# moire_v2_4.net
KiCad netlist of a schematic drawn in EAGLE
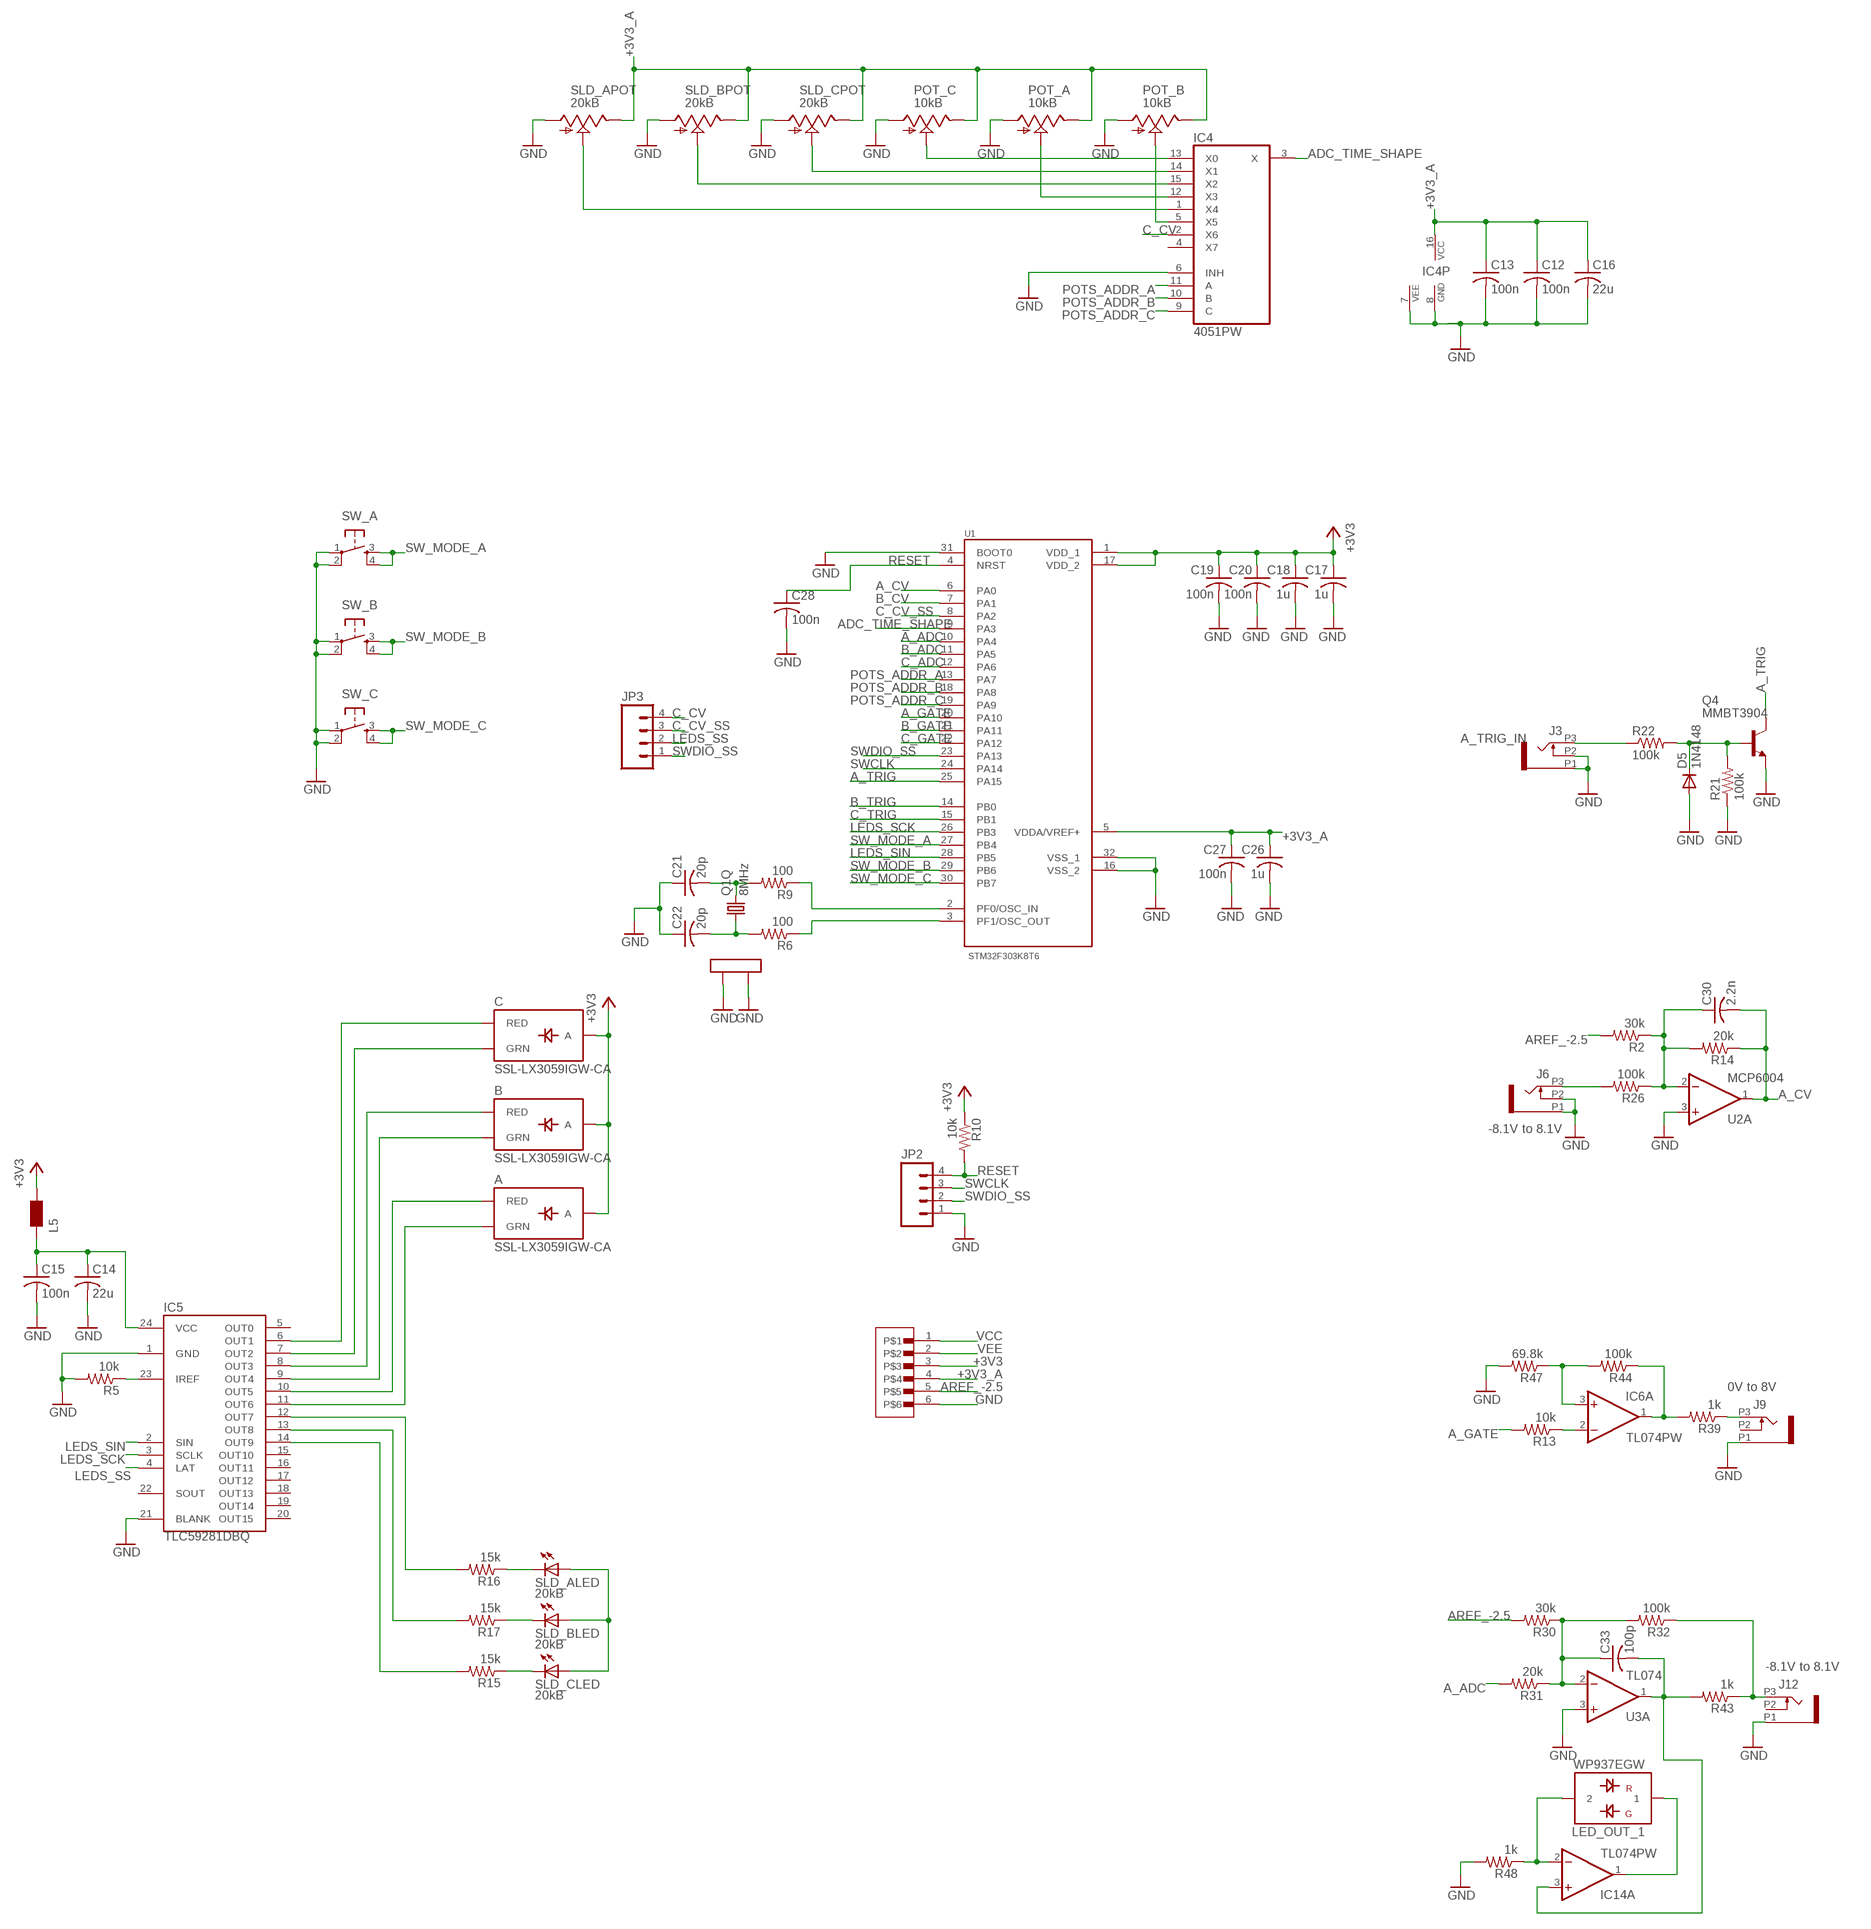
[diagram p0: schematic, sheet 1, part 1 of 2]
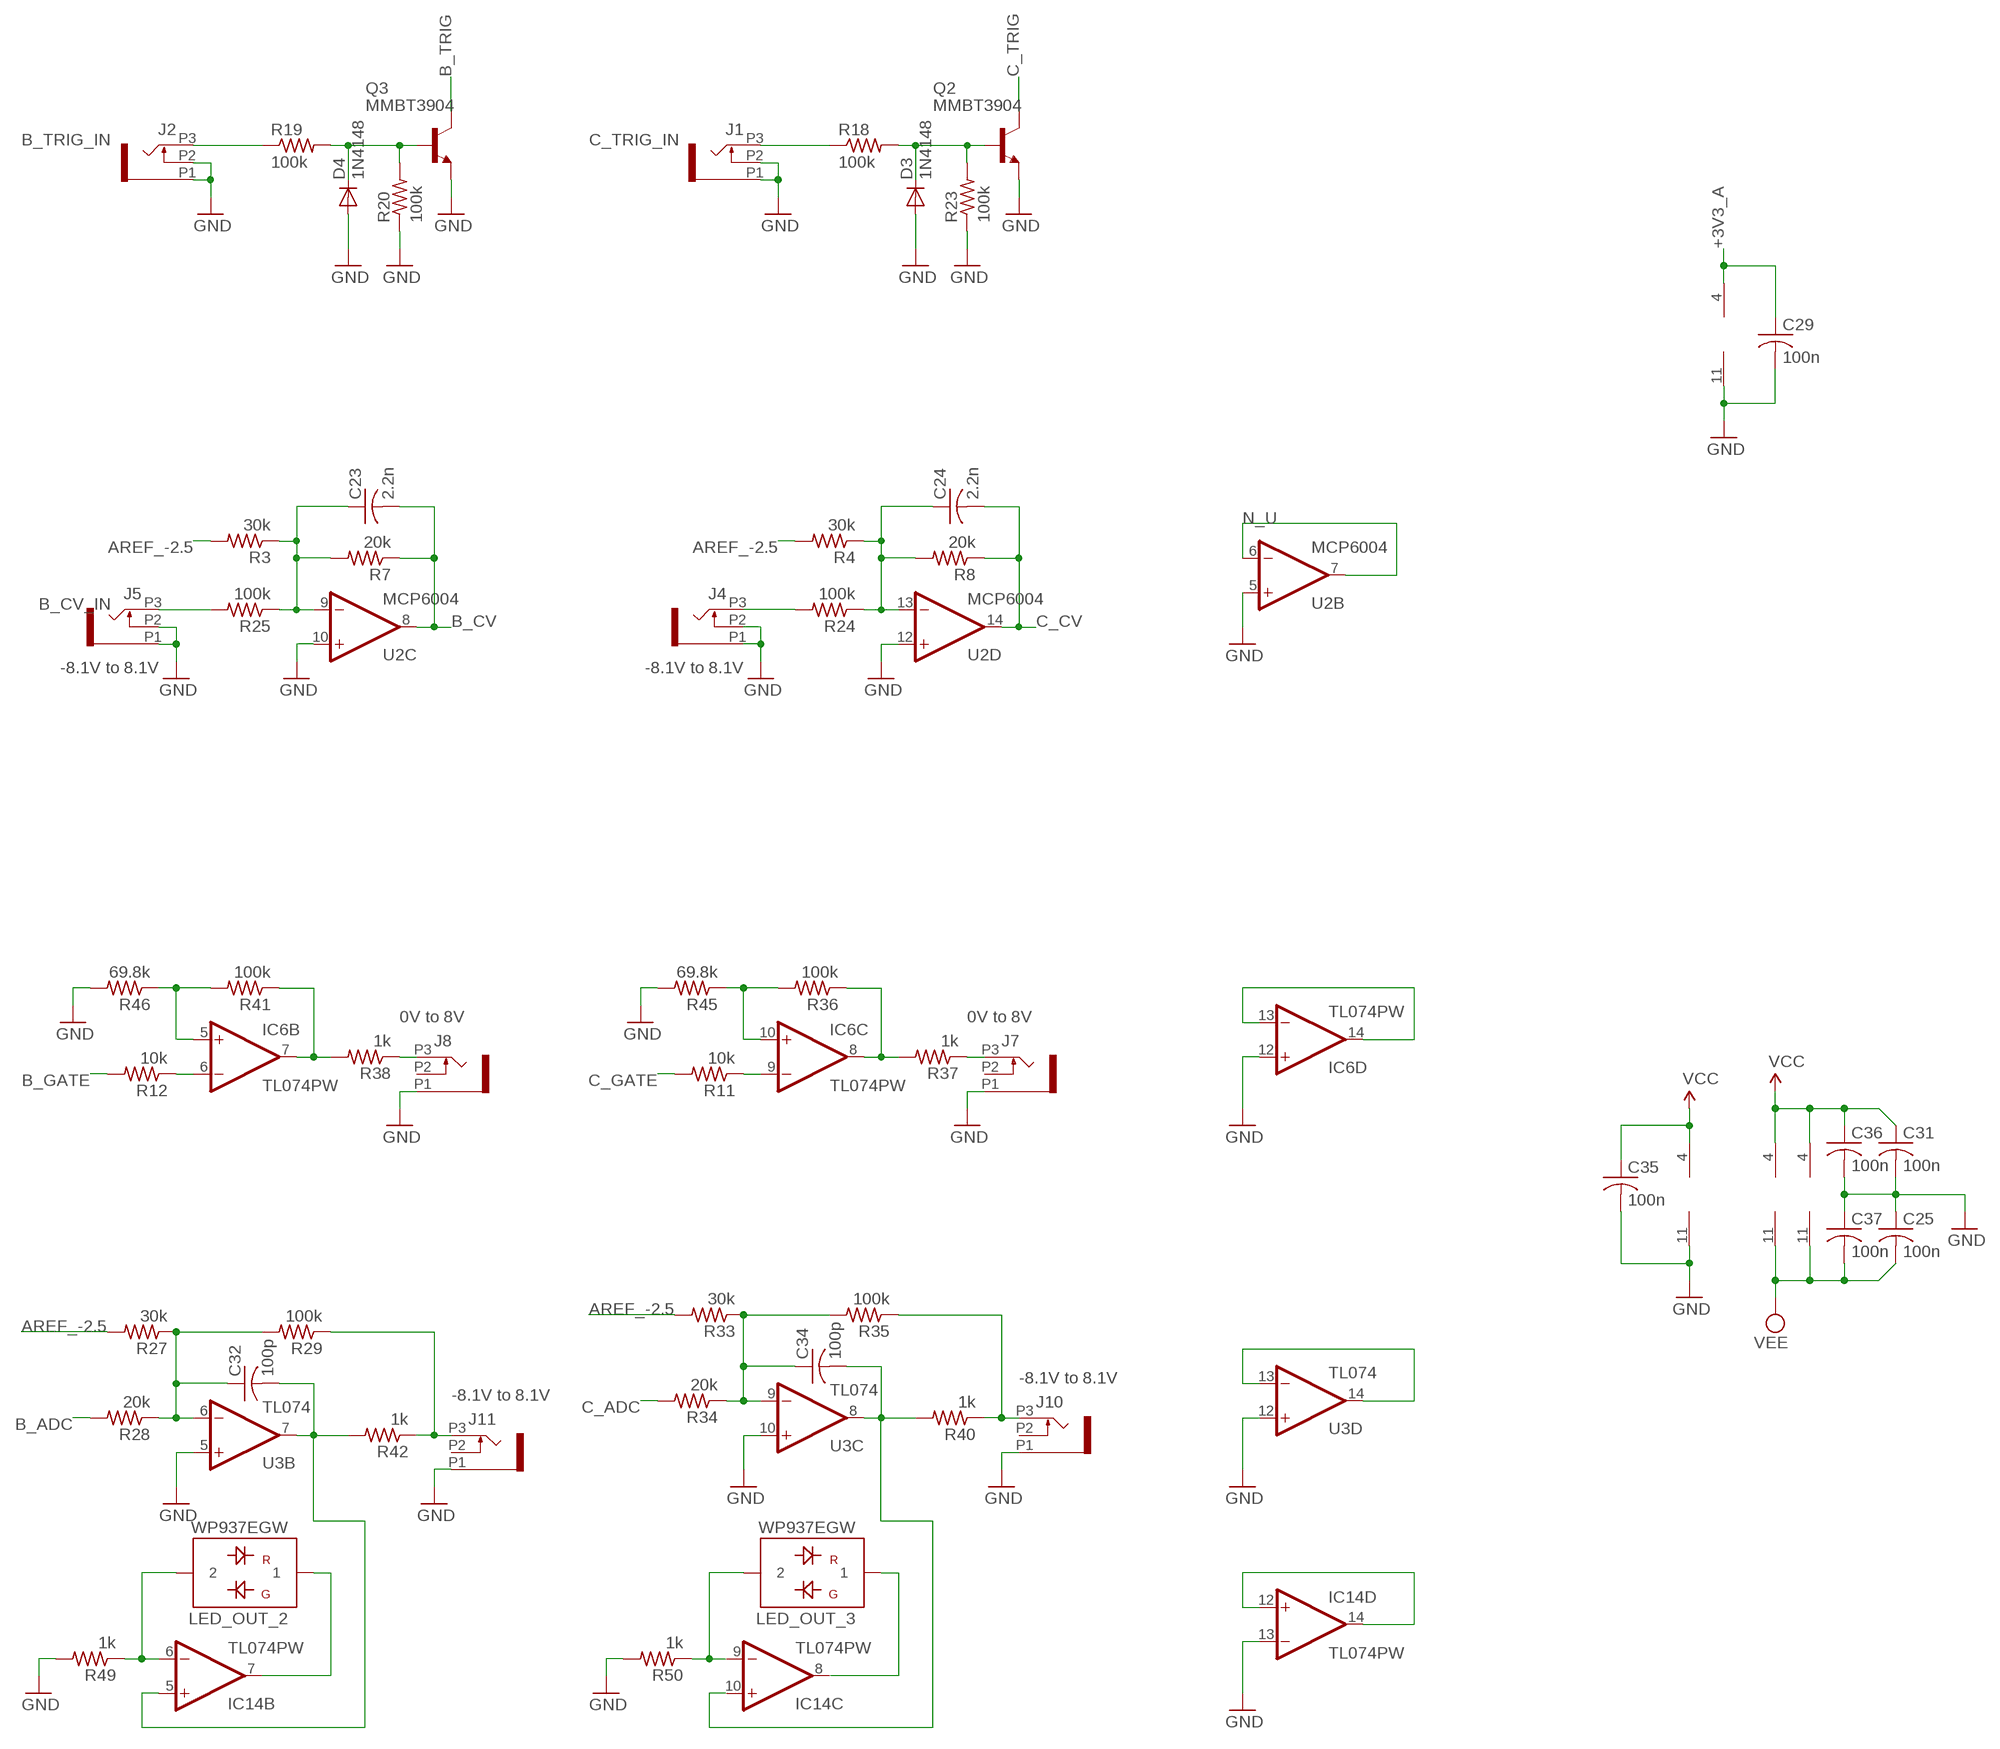
[diagram p1: schematic, sheet 1, part 2 of 2]
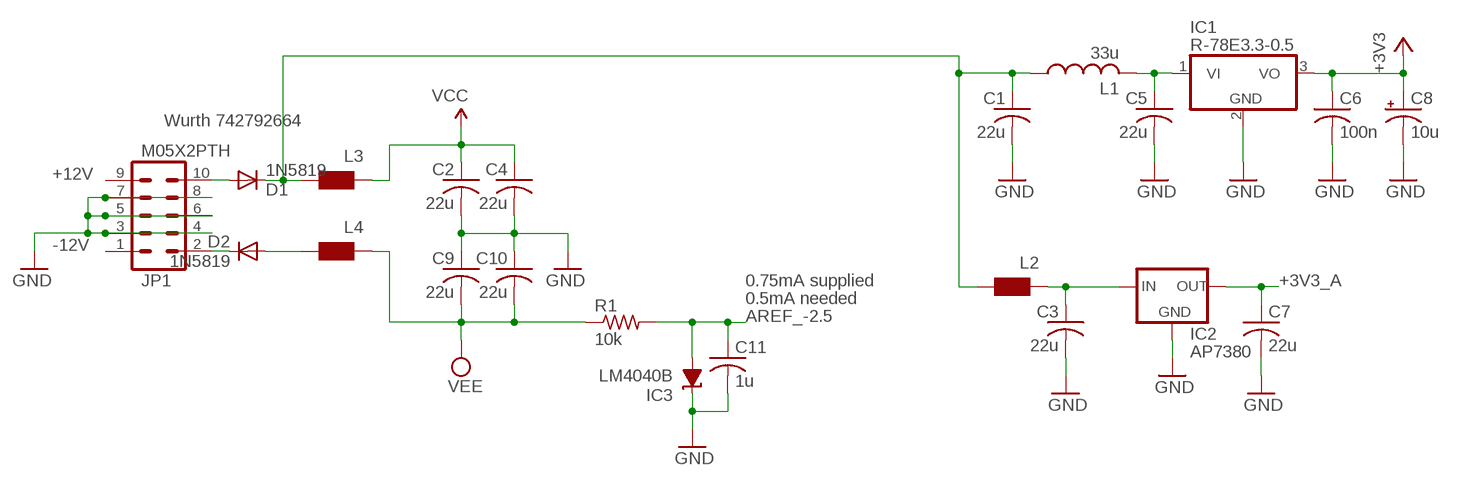
[diagram p2: schematic, sheet 2]

(export (version "E")
  (design (tool "Eeschema 10.0.6"))
  (components
    (comp (ref "C1")
      (value "22u")
      (footprint "eagle-import:RCL_C1206")
      (libsource (lib "eagle-import") (part "RCL_C-USC1206"))
    )
    (comp (ref "C2")
      (value "22u")
      (footprint "eagle-import:RCL_C1206")
      (libsource (lib "eagle-import") (part "RCL_C-USC1206"))
    )
    (comp (ref "C3")
      (value "22u")
      (footprint "eagle-import:RCL_C1206")
      (libsource (lib "eagle-import") (part "RCL_C-USC1206"))
    )
    (comp (ref "C4")
      (value "22u")
      (footprint "eagle-import:RCL_C1206")
      (libsource (lib "eagle-import") (part "RCL_C-USC1206"))
    )
    (comp (ref "C5")
      (value "22u")
      (footprint "eagle-import:RCL_C1206")
      (libsource (lib "eagle-import") (part "RCL_C-USC1206"))
    )
    (comp (ref "C6")
      (value "100n")
      (footprint "eagle-import:RCL_C0603")
      (libsource (lib "eagle-import") (part "RCL_C-USC0603"))
    )
    (comp (ref "C7")
      (value "22u")
      (footprint "eagle-import:RCL_C1206")
      (libsource (lib "eagle-import") (part "RCL_C-USC1206"))
    )
    (comp (ref "C8")
      (value "10u")
      (footprint "eagle-import:RCL_PANASONIC_A")
      (libsource (lib "eagle-import") (part "RCL_CPOL-USA"))
    )
    (comp (ref "C9")
      (value "22u")
      (footprint "eagle-import:RCL_C1206")
      (libsource (lib "eagle-import") (part "RCL_C-USC1206"))
    )
    (comp (ref "C10")
      (value "22u")
      (footprint "eagle-import:RCL_C1206")
      (libsource (lib "eagle-import") (part "RCL_C-USC1206"))
    )
    (comp (ref "C11")
      (value "1u")
      (footprint "eagle-import:RCL_C0603")
      (libsource (lib "eagle-import") (part "RCL_C-USC0603"))
    )
    (comp (ref "D1")
      (value "1N5819")
      (footprint "eagle-import:DIODE_SOD123")
      (libsource (lib "eagle-import") (part "DIODE_DIODE-SOD123"))
    )
    (comp (ref "D2")
      (value "1N5819")
      (footprint "eagle-import:DIODE_SOD123")
      (libsource (lib "eagle-import") (part "DIODE_DIODE-SOD123"))
    )
    (comp (ref "IC1")
      (value "R-78E3.3-0.5")
      (footprint "eagle-import:WE78")
      (libsource (lib "eagle-import") (part "WE173950378"))
    )
    (comp (ref "IC2")
      (value "AP7380")
      (footprint "eagle-import:SOT89")
      (libsource (lib "eagle-import") (part "AP7380"))
    )
    (comp (ref "IC3")
      (value "LM4040B")
      (footprint "eagle-import:DBZ_R-PDSO-G3")
      (libsource (lib "eagle-import") (part "LM4041DBZB12"))
    )
    (comp (ref "JP1")
      (value "M05X2PTH")
      (footprint "eagle-import:2X5-PTH")
      (libsource (lib "eagle-import") (part "M05X2PTH"))
    )
    (comp (ref "L1")
      (value "33u")
      (footprint "eagle-import:L2012C")
      (libsource (lib "eagle-import") (part "L-USL2012C"))
    )
    (comp (ref "L2")
      (value "WE-CBF_0603")
      (footprint "eagle-import:0603")
      (libsource (lib "eagle-import") (part "WE-CBF_0603"))
    )
    (comp (ref "L3")
      (value "WE-CBF_0603")
      (footprint "eagle-import:0603")
      (libsource (lib "eagle-import") (part "WE-CBF_0603"))
    )
    (comp (ref "L4")
      (value "WE-CBF_0603")
      (footprint "eagle-import:0603")
      (libsource (lib "eagle-import") (part "WE-CBF_0603"))
    )
    (comp (ref "R1")
      (value "10k")
      (footprint "eagle-import:RCL_R0603")
      (libsource (lib "eagle-import") (part "RCL_R-US_R0603"))
    )
    (comp (ref "A")
      (value "SSL-LX3059IGW-CA")
      (footprint "eagle-import:LED-BICOLOR-THROUGHHOLE-LUMEX")
      (libsource (lib "eagle-import") (part "LED-BICOLOR-THROUGHHOLE-CA"))
    )
    (comp (ref "B")
      (value "SSL-LX3059IGW-CA")
      (footprint "eagle-import:LED-BICOLOR-THROUGHHOLE-LUMEX")
      (libsource (lib "eagle-import") (part "LED-BICOLOR-THROUGHHOLE-CA"))
    )
    (comp (ref "C")
      (value "SSL-LX3059IGW-CA")
      (footprint "eagle-import:LED-BICOLOR-THROUGHHOLE-LUMEX")
      (libsource (lib "eagle-import") (part "LED-BICOLOR-THROUGHHOLE-CA"))
    )
    (comp (ref "C12")
      (value "100n")
      (footprint "eagle-import:RCL_C0603")
      (libsource (lib "eagle-import") (part "RCL_C-USC0603"))
    )
    (comp (ref "C13")
      (value "100n")
      (footprint "eagle-import:RCL_C0603")
      (libsource (lib "eagle-import") (part "RCL_C-USC0603"))
    )
    (comp (ref "C14")
      (value "22u")
      (footprint "eagle-import:RCL_C1206")
      (libsource (lib "eagle-import") (part "RCL_C-USC1206"))
    )
    (comp (ref "C15")
      (value "100n")
      (footprint "eagle-import:RCL_C0603")
      (libsource (lib "eagle-import") (part "RCL_C-USC0603"))
    )
    (comp (ref "C16")
      (value "22u")
      (footprint "eagle-import:RCL_C1206")
      (libsource (lib "eagle-import") (part "RCL_C-USC1206"))
    )
    (comp (ref "C17")
      (value "1u")
      (footprint "eagle-import:RCL_C0603")
      (libsource (lib "eagle-import") (part "RCL_C-USC0603"))
    )
    (comp (ref "C18")
      (value "1u")
      (footprint "eagle-import:RCL_C0603")
      (libsource (lib "eagle-import") (part "RCL_C-USC0603"))
    )
    (comp (ref "C19")
      (value "100n")
      (footprint "eagle-import:RCL_C0603")
      (libsource (lib "eagle-import") (part "RCL_C-USC0603"))
    )
    (comp (ref "C20")
      (value "100n")
      (footprint "eagle-import:RCL_C0603")
      (libsource (lib "eagle-import") (part "RCL_C-USC0603"))
    )
    (comp (ref "C21")
      (value "20p")
      (footprint "eagle-import:RCL_C0603")
      (libsource (lib "eagle-import") (part "RCL_C-USC0603"))
    )
    (comp (ref "C22")
      (value "20p")
      (footprint "eagle-import:RCL_C0603")
      (libsource (lib "eagle-import") (part "RCL_C-USC0603"))
    )
    (comp (ref "C23")
      (value "2.2n")
      (footprint "eagle-import:RCL_C0603")
      (libsource (lib "eagle-import") (part "RCL_C-USC0603"))
    )
    (comp (ref "C24")
      (value "2.2n")
      (footprint "eagle-import:RCL_C0603")
      (libsource (lib "eagle-import") (part "RCL_C-USC0603"))
    )
    (comp (ref "C25")
      (value "100n")
      (footprint "eagle-import:RCL_C0603")
      (libsource (lib "eagle-import") (part "RCL_C-USC0603"))
    )
    (comp (ref "C26")
      (value "1u")
      (footprint "eagle-import:RCL_C0603")
      (libsource (lib "eagle-import") (part "RCL_C-USC0603"))
    )
    (comp (ref "C27")
      (value "100n")
      (footprint "eagle-import:RCL_C0603")
      (libsource (lib "eagle-import") (part "RCL_C-USC0603"))
    )
    (comp (ref "C28")
      (value "100n")
      (footprint "eagle-import:RCL_C0603")
      (libsource (lib "eagle-import") (part "RCL_C-USC0603"))
    )
    (comp (ref "C29")
      (value "100n")
      (footprint "eagle-import:RCL_C0603")
      (libsource (lib "eagle-import") (part "RCL_C-USC0603"))
    )
    (comp (ref "C30")
      (value "2.2n")
      (footprint "eagle-import:RCL_C0603")
      (libsource (lib "eagle-import") (part "RCL_C-USC0603"))
    )
    (comp (ref "C31")
      (value "100n")
      (footprint "eagle-import:RCL_C0603")
      (libsource (lib "eagle-import") (part "RCL_C-USC0603"))
    )
    (comp (ref "C32")
      (value "100p")
      (footprint "eagle-import:RCL_C0603")
      (libsource (lib "eagle-import") (part "RCL_C-USC0603"))
    )
    (comp (ref "C33")
      (value "100p")
      (footprint "eagle-import:RCL_C0603")
      (libsource (lib "eagle-import") (part "RCL_C-USC0603"))
    )
    (comp (ref "C34")
      (value "100p")
      (footprint "eagle-import:RCL_C0603")
      (libsource (lib "eagle-import") (part "RCL_C-USC0603"))
    )
    (comp (ref "C35")
      (value "100n")
      (footprint "eagle-import:RCL_C0603")
      (libsource (lib "eagle-import") (part "RCL_C-USC0603"))
    )
    (comp (ref "C36")
      (value "100n")
      (footprint "eagle-import:RCL_C0603")
      (libsource (lib "eagle-import") (part "RCL_C-USC0603"))
    )
    (comp (ref "C37")
      (value "100n")
      (footprint "eagle-import:RCL_C0603")
      (libsource (lib "eagle-import") (part "RCL_C-USC0603"))
    )
    (comp (ref "D3")
      (value "1N4148")
      (footprint "eagle-import:DIODE_SOD523")
      (libsource (lib "eagle-import") (part "DIODE_DIODE-SOD523"))
    )
    (comp (ref "D4")
      (value "1N4148")
      (footprint "eagle-import:DIODE_SOD523")
      (libsource (lib "eagle-import") (part "DIODE_DIODE-SOD523"))
    )
    (comp (ref "D5")
      (value "1N4148")
      (footprint "eagle-import:DIODE_SOD523")
      (libsource (lib "eagle-import") (part "DIODE_DIODE-SOD523"))
    )
    (comp (ref "IC4")
      (value "4051PW")
      (footprint "eagle-import:TSSOP16_065")
      (libsource (lib "eagle-import") (part "4051PW"))
    )
    (comp (ref "IC5")
      (value "TLC59281DBQ")
      (footprint "eagle-import:TSSOP24_0635")
      (libsource (lib "eagle-import") (part "TLC59281DBQ"))
    )
    (comp (ref "IC6")
      (value "TL074PW")
      (footprint "eagle-import:TSSOP14_065")
      (libsource (lib "eagle-import") (part "og-linear_TL074PW"))
    )
    (comp (ref "IC14")
      (value "TL074PW")
      (footprint "eagle-import:TSSOP14_065")
      (libsource (lib "eagle-import") (part "TL074PW"))
    )
    (comp (ref "J1")
      (value "PJ301_THONKICONN6")
      (footprint "eagle-import:WQP_PJ_301M6")
      (libsource (lib "eagle-import") (part "PJ301_THONKICONN6"))
    )
    (comp (ref "J2")
      (value "PJ301_THONKICONN6")
      (footprint "eagle-import:WQP_PJ_301M6")
      (libsource (lib "eagle-import") (part "PJ301_THONKICONN6"))
    )
    (comp (ref "J3")
      (value "PJ301_THONKICONN6")
      (footprint "eagle-import:WQP_PJ_301M6")
      (libsource (lib "eagle-import") (part "PJ301_THONKICONN6"))
    )
    (comp (ref "J4")
      (value "PJ301_THONKICONN6")
      (footprint "eagle-import:WQP_PJ_301M6")
      (libsource (lib "eagle-import") (part "PJ301_THONKICONN6"))
    )
    (comp (ref "J5")
      (value "PJ301_THONKICONN6")
      (footprint "eagle-import:WQP_PJ_301M6")
      (libsource (lib "eagle-import") (part "PJ301_THONKICONN6"))
    )
    (comp (ref "J6")
      (value "PJ301_THONKICONN6")
      (footprint "eagle-import:WQP_PJ_301M6")
      (libsource (lib "eagle-import") (part "PJ301_THONKICONN6"))
    )
    (comp (ref "J7")
      (value "PJ301_THONKICONN6")
      (footprint "eagle-import:WQP_PJ_301M6")
      (libsource (lib "eagle-import") (part "PJ301_THONKICONN6"))
    )
    (comp (ref "J8")
      (value "PJ301_THONKICONN6")
      (footprint "eagle-import:WQP_PJ_301M6")
      (libsource (lib "eagle-import") (part "PJ301_THONKICONN6"))
    )
    (comp (ref "J9")
      (value "PJ301_THONKICONN6")
      (footprint "eagle-import:WQP_PJ_301M6")
      (libsource (lib "eagle-import") (part "PJ301_THONKICONN6"))
    )
    (comp (ref "J10")
      (value "PJ301_THONKICONN6")
      (footprint "eagle-import:WQP_PJ_301M6")
      (libsource (lib "eagle-import") (part "PJ301_THONKICONN6"))
    )
    (comp (ref "J11")
      (value "PJ301_THONKICONN6")
      (footprint "eagle-import:WQP_PJ_301M6")
      (libsource (lib "eagle-import") (part "PJ301_THONKICONN6"))
    )
    (comp (ref "J12")
      (value "PJ301_THONKICONN6")
      (footprint "eagle-import:WQP_PJ_301M6")
      (libsource (lib "eagle-import") (part "PJ301_THONKICONN6"))
    )
    (comp (ref "JP2")
      (value "M04PTH")
      (footprint "eagle-import:1X04")
      (libsource (lib "eagle-import") (part "M04PTH"))
    )
    (comp (ref "JP3")
      (value "M04PTH")
      (footprint "eagle-import:1X04")
      (libsource (lib "eagle-import") (part "M04PTH"))
    )
    (comp (ref "L5")
      (value "WE-CBF_0603")
      (footprint "eagle-import:0603")
      (libsource (lib "eagle-import") (part "WE-CBF_0603"))
    )
    (comp (ref "LED_OUT_1")
      (value "WP937EGW")
      (footprint "eagle-import:LED3MM")
      (libsource (lib "eagle-import") (part "LED-BICOLOR-SHARED-THROUGHHOLE"))
    )
    (comp (ref "LED_OUT_2")
      (value "WP937EGW")
      (footprint "eagle-import:LED3MM")
      (libsource (lib "eagle-import") (part "LED-BICOLOR-SHARED-THROUGHHOLE"))
    )
    (comp (ref "LED_OUT_3")
      (value "WP937EGW")
      (footprint "eagle-import:LED3MM")
      (libsource (lib "eagle-import") (part "LED-BICOLOR-SHARED-THROUGHHOLE"))
    )
    (comp (ref "POT_A")
      (value "10kB")
      (footprint "eagle-import:ALPS_POT_VERTICAL")
      (libsource (lib "eagle-import") (part "POT_USVERTICAL"))
    )
    (comp (ref "POT_B")
      (value "10kB")
      (footprint "eagle-import:ALPS_POT_VERTICAL")
      (libsource (lib "eagle-import") (part "POT_USVERTICAL"))
    )
    (comp (ref "POT_C")
      (value "10kB")
      (footprint "eagle-import:ALPS_POT_VERTICAL")
      (libsource (lib "eagle-import") (part "POT_USVERTICAL"))
    )
    (comp (ref "Q1")
      (value "8MHz")
      (footprint "eagle-import:CTS406")
      (libsource (lib "eagle-import") (part "CRYSTAL"))
    )
    (comp (ref "Q2")
      (value "MMBT3904")
      (footprint "eagle-import:SOT23-BEC")
      (libsource (lib "eagle-import") (part "-NPN-SOT23-BECMMBT3904LT1"))
    )
    (comp (ref "Q3")
      (value "MMBT3904")
      (footprint "eagle-import:SOT23-BEC")
      (libsource (lib "eagle-import") (part "-NPN-SOT23-BECMMBT3904LT1"))
    )
    (comp (ref "Q4")
      (value "MMBT3904")
      (footprint "eagle-import:SOT23-BEC")
      (libsource (lib "eagle-import") (part "-NPN-SOT23-BECMMBT3904LT1"))
    )
    (comp (ref "R2")
      (value "30k")
      (footprint "eagle-import:RCL_R0603")
      (libsource (lib "eagle-import") (part "RCL_R-US_R0603"))
    )
    (comp (ref "R3")
      (value "30k")
      (footprint "eagle-import:RCL_R0603")
      (libsource (lib "eagle-import") (part "RCL_R-US_R0603"))
    )
    (comp (ref "R4")
      (value "30k")
      (footprint "eagle-import:RCL_R0603")
      (libsource (lib "eagle-import") (part "RCL_R-US_R0603"))
    )
    (comp (ref "R5")
      (value "10k")
      (footprint "eagle-import:RCL_R0603")
      (libsource (lib "eagle-import") (part "RCL_R-US_R0603"))
    )
    (comp (ref "R6")
      (value "100")
      (footprint "eagle-import:RCL_R0603")
      (libsource (lib "eagle-import") (part "RCL_R-US_R0603"))
    )
    (comp (ref "R7")
      (value "20k")
      (footprint "eagle-import:RCL_R0603")
      (libsource (lib "eagle-import") (part "RCL_R-US_R0603"))
    )
    (comp (ref "R8")
      (value "20k")
      (footprint "eagle-import:RCL_R0603")
      (libsource (lib "eagle-import") (part "RCL_R-US_R0603"))
    )
    (comp (ref "R9")
      (value "100")
      (footprint "eagle-import:RCL_R0603")
      (libsource (lib "eagle-import") (part "RCL_R-US_R0603"))
    )
    (comp (ref "R10")
      (value "10k")
      (footprint "eagle-import:RCL_R0603")
      (libsource (lib "eagle-import") (part "RCL_R-US_R0603"))
    )
    (comp (ref "R11")
      (value "10k")
      (footprint "eagle-import:RCL_R0603")
      (libsource (lib "eagle-import") (part "RCL_R-US_R0603"))
    )
    (comp (ref "R12")
      (value "10k")
      (footprint "eagle-import:RCL_R0603")
      (libsource (lib "eagle-import") (part "RCL_R-US_R0603"))
    )
    (comp (ref "R13")
      (value "10k")
      (footprint "eagle-import:RCL_R0603")
      (libsource (lib "eagle-import") (part "RCL_R-US_R0603"))
    )
    (comp (ref "R14")
      (value "20k")
      (footprint "eagle-import:RCL_R0603")
      (libsource (lib "eagle-import") (part "RCL_R-US_R0603"))
    )
    (comp (ref "R15")
      (value "15k")
      (footprint "eagle-import:RCL_R0603")
      (libsource (lib "eagle-import") (part "RCL_R-US_R0603"))
    )
    (comp (ref "R16")
      (value "15k")
      (footprint "eagle-import:RCL_R0603")
      (libsource (lib "eagle-import") (part "RCL_R-US_R0603"))
    )
    (comp (ref "R17")
      (value "15k")
      (footprint "eagle-import:RCL_R0603")
      (libsource (lib "eagle-import") (part "RCL_R-US_R0603"))
    )
    (comp (ref "R18")
      (value "100k")
      (footprint "eagle-import:RCL_R0603")
      (libsource (lib "eagle-import") (part "RCL_R-US_R0603"))
    )
    (comp (ref "R19")
      (value "100k")
      (footprint "eagle-import:RCL_R0603")
      (libsource (lib "eagle-import") (part "RCL_R-US_R0603"))
    )
    (comp (ref "R20")
      (value "100k")
      (footprint "eagle-import:RCL_R0603")
      (libsource (lib "eagle-import") (part "RCL_R-US_R0603"))
    )
    (comp (ref "R21")
      (value "100k")
      (footprint "eagle-import:RCL_R0603")
      (libsource (lib "eagle-import") (part "RCL_R-US_R0603"))
    )
    (comp (ref "R22")
      (value "100k")
      (footprint "eagle-import:RCL_R0603")
      (libsource (lib "eagle-import") (part "RCL_R-US_R0603"))
    )
    (comp (ref "R23")
      (value "100k")
      (footprint "eagle-import:RCL_R0603")
      (libsource (lib "eagle-import") (part "RCL_R-US_R0603"))
    )
    (comp (ref "R24")
      (value "100k")
      (footprint "eagle-import:RCL_R0603")
      (libsource (lib "eagle-import") (part "RCL_R-US_R0603"))
    )
    (comp (ref "R25")
      (value "100k")
      (footprint "eagle-import:RCL_R0603")
      (libsource (lib "eagle-import") (part "RCL_R-US_R0603"))
    )
    (comp (ref "R26")
      (value "100k")
      (footprint "eagle-import:RCL_R0603")
      (libsource (lib "eagle-import") (part "RCL_R-US_R0603"))
    )
    (comp (ref "R27")
      (value "30k")
      (footprint "eagle-import:RCL_R0603")
      (libsource (lib "eagle-import") (part "RCL_R-US_R0603"))
    )
    (comp (ref "R28")
      (value "20k")
      (footprint "eagle-import:RCL_R0603")
      (libsource (lib "eagle-import") (part "RCL_R-US_R0603"))
    )
    (comp (ref "R29")
      (value "100k")
      (footprint "eagle-import:RCL_R0603")
      (libsource (lib "eagle-import") (part "RCL_R-US_R0603"))
    )
    (comp (ref "R30")
      (value "30k")
      (footprint "eagle-import:RCL_R0603")
      (libsource (lib "eagle-import") (part "RCL_R-US_R0603"))
    )
    (comp (ref "R31")
      (value "20k")
      (footprint "eagle-import:RCL_R0603")
      (libsource (lib "eagle-import") (part "RCL_R-US_R0603"))
    )
    (comp (ref "R32")
      (value "100k")
      (footprint "eagle-import:RCL_R0603")
      (libsource (lib "eagle-import") (part "RCL_R-US_R0603"))
    )
    (comp (ref "R33")
      (value "30k")
      (footprint "eagle-import:RCL_R0603")
      (libsource (lib "eagle-import") (part "RCL_R-US_R0603"))
    )
    (comp (ref "R34")
      (value "20k")
      (footprint "eagle-import:RCL_R0603")
      (libsource (lib "eagle-import") (part "RCL_R-US_R0603"))
    )
    (comp (ref "R35")
      (value "100k")
      (footprint "eagle-import:RCL_R0603")
      (libsource (lib "eagle-import") (part "RCL_R-US_R0603"))
    )
    (comp (ref "R36")
      (value "100k")
      (footprint "eagle-import:RCL_R0603")
      (libsource (lib "eagle-import") (part "RCL_R-US_R0603"))
    )
    (comp (ref "R37")
      (value "1k")
      (footprint "eagle-import:RCL_R0603")
      (libsource (lib "eagle-import") (part "RCL_R-US_R0603"))
    )
    (comp (ref "R38")
      (value "1k")
      (footprint "eagle-import:RCL_R0603")
      (libsource (lib "eagle-import") (part "RCL_R-US_R0603"))
    )
    (comp (ref "R39")
      (value "1k")
      (footprint "eagle-import:RCL_R0603")
      (libsource (lib "eagle-import") (part "RCL_R-US_R0603"))
    )
    (comp (ref "R40")
      (value "1k")
      (footprint "eagle-import:RCL_R0603")
      (libsource (lib "eagle-import") (part "RCL_R-US_R0603"))
    )
    (comp (ref "R41")
      (value "100k")
      (footprint "eagle-import:RCL_R0603")
      (libsource (lib "eagle-import") (part "RCL_R-US_R0603"))
    )
    (comp (ref "R42")
      (value "1k")
      (footprint "eagle-import:RCL_R0603")
      (libsource (lib "eagle-import") (part "RCL_R-US_R0603"))
    )
    (comp (ref "R43")
      (value "1k")
      (footprint "eagle-import:RCL_R0603")
      (libsource (lib "eagle-import") (part "RCL_R-US_R0603"))
    )
    (comp (ref "R44")
      (value "100k")
      (footprint "eagle-import:RCL_R0603")
      (libsource (lib "eagle-import") (part "RCL_R-US_R0603"))
    )
    (comp (ref "R45")
      (value "69.8k")
      (footprint "eagle-import:RCL_R0603")
      (libsource (lib "eagle-import") (part "RCL_R-US_R0603"))
    )
    (comp (ref "R46")
      (value "69.8k")
      (footprint "eagle-import:RCL_R0603")
      (libsource (lib "eagle-import") (part "RCL_R-US_R0603"))
    )
    (comp (ref "R47")
      (value "69.8k")
      (footprint "eagle-import:RCL_R0603")
      (libsource (lib "eagle-import") (part "RCL_R-US_R0603"))
    )
    (comp (ref "R48")
      (value "1k")
      (footprint "eagle-import:RCL_R0603")
      (libsource (lib "eagle-import") (part "RCL_R-US_R0603"))
    )
    (comp (ref "R49")
      (value "1k")
      (footprint "eagle-import:RCL_R0603")
      (libsource (lib "eagle-import") (part "RCL_R-US_R0603"))
    )
    (comp (ref "R50")
      (value "1k")
      (footprint "eagle-import:RCL_R0603")
      (libsource (lib "eagle-import") (part "RCL_R-US_R0603"))
    )
    (comp (ref "SLD_A")
      (value "20kB")
      (footprint "eagle-import:BOURNS_SLIDER")
      (libsource (lib "eagle-import") (part "BOURNS_SLIDER"))
    )
    (comp (ref "SLD_B")
      (value "20kB")
      (footprint "eagle-import:BOURNS_SLIDER")
      (libsource (lib "eagle-import") (part "BOURNS_SLIDER"))
    )
    (comp (ref "SLD_C")
      (value "20kB")
      (footprint "eagle-import:BOURNS_SLIDER")
      (libsource (lib "eagle-import") (part "BOURNS_SLIDER"))
    )
    (comp (ref "SW_A")
      (value "TAC_SWITCHPTH")
      (footprint "eagle-import:TACTILE-PTH")
      (libsource (lib "eagle-import") (part "TAC_SWITCHPTH"))
    )
    (comp (ref "SW_B")
      (value "TAC_SWITCHPTH")
      (footprint "eagle-import:TACTILE-PTH")
      (libsource (lib "eagle-import") (part "TAC_SWITCHPTH"))
    )
    (comp (ref "SW_C")
      (value "TAC_SWITCHPTH")
      (footprint "eagle-import:TACTILE-PTH")
      (libsource (lib "eagle-import") (part "TAC_SWITCHPTH"))
    )
    (comp (ref "U$1")
      (value "1X6-SMD-TESTPAD")
      (footprint "eagle-import:6X1-SMD-TESTPAD")
      (libsource (lib "eagle-import") (part "1X6-SMD-TESTPAD"))
    )
    (comp (ref "U1")
      (value "STM32F303K8T6")
      (footprint "eagle-import:QFP80P900X900X160-32N")
      (fields (field (name "MF") "STMicroelectronics"))
      (libsource (lib "eagle-import") (part "STM32F303K8T6"))
    )
    (comp (ref "U2")
      (value "MCP6004")
      (footprint "eagle-import:SO14")
      (libsource (lib "eagle-import") (part "MCP6004_SMD"))
    )
    (comp (ref "U3")
      (value "TL074")
      (footprint "eagle-import:SO14")
      (libsource (lib "eagle-import") (part "TL074_SMD"))
    )
  )
  (nets
    (net (code "1") (name "+3V3") (class "Default")
      (node (ref "A") (pin "A") (pinfunction "A_A") (pintype "bidirectional"))
      (node (ref "B") (pin "A") (pinfunction "A_A") (pintype "bidirectional"))
      (node (ref "C") (pin "A") (pinfunction "A_A") (pintype "bidirectional"))
      (node (ref "C17") (pin "1") (pinfunction "1_1") (pintype "passive"))
      (node (ref "C18") (pin "1") (pinfunction "1_1") (pintype "passive"))
      (node (ref "C19") (pin "1") (pinfunction "1_1") (pintype "passive"))
      (node (ref "C20") (pin "1") (pinfunction "1_1") (pintype "passive"))
      (node (ref "C6") (pin "1") (pinfunction "1_1") (pintype "passive"))
      (node (ref "C8") (pin "+") (pinfunction "+_+") (pintype "passive"))
      (node (ref "IC1") (pin "3") (pinfunction "VO_3") (pintype "passive"))
      (node (ref "L5") (pin "2") (pinfunction "2_2") (pintype "passive"))
      (node (ref "R10") (pin "1") (pinfunction "1_1") (pintype "passive"))
      (node (ref "U$1") (pin "3") (pinfunction "P$3_3") (pintype "bidirectional"))
      (node (ref "U1") (pin "1") (pinfunction "VDD_1_1") (pintype "power_in"))
      (node (ref "U1") (pin "17") (pinfunction "VDD_2_17") (pintype "power_in"))
    )
    (net (code "2") (name "+3V3_A") (class "Default")
      (node (ref "C12") (pin "1") (pinfunction "1_1") (pintype "passive"))
      (node (ref "C13") (pin "1") (pinfunction "1_1") (pintype "passive"))
      (node (ref "C16") (pin "1") (pinfunction "1_1") (pintype "passive"))
      (node (ref "C26") (pin "1") (pinfunction "1_1") (pintype "passive"))
      (node (ref "C27") (pin "1") (pinfunction "1_1") (pintype "passive"))
      (node (ref "C29") (pin "1") (pinfunction "1_1") (pintype "passive"))
      (node (ref "C7") (pin "1") (pinfunction "1_1") (pintype "passive"))
      (node (ref "IC2") (pin "3") (pinfunction "OUT_3") (pintype "passive"))
      (node (ref "IC4") (pin "16") (pinfunction "VCC_16") (pintype "power_in"))
      (node (ref "POT_A") (pin "P$1") (pinfunction "E_P$1") (pintype "passive"))
      (node (ref "POT_B") (pin "P$1") (pinfunction "E_P$1") (pintype "passive"))
      (node (ref "POT_C") (pin "P$1") (pinfunction "E_P$1") (pintype "passive"))
      (node (ref "SLD_A") (pin "3") (pinfunction "E_3") (pintype "passive"))
      (node (ref "SLD_B") (pin "3") (pinfunction "E_3") (pintype "passive"))
      (node (ref "SLD_C") (pin "3") (pinfunction "E_3") (pintype "passive"))
      (node (ref "U$1") (pin "4") (pinfunction "P$4_4") (pintype "bidirectional"))
      (node (ref "U1") (pin "5") (pinfunction "VDDA/VREF+_5") (pintype "power_in"))
      (node (ref "U2") (pin "4") (pinfunction "V+_4") (pintype "power_in"))
    )
    (net (code "3") (name "+12V") (class "Default")
      (node (ref "D1") (pin "A") (pinfunction "A_A") (pintype "passive"))
      (node (ref "JP1") (pin "10") (pinfunction "10_10") (pintype "passive"))
      (node (ref "JP1") (pin "9") (pinfunction "9_9") (pintype "passive"))
    )
    (net (code "4") (name "-12V") (class "Default")
      (node (ref "D2") (pin "C") (pinfunction "C_C") (pintype "passive"))
      (node (ref "JP1") (pin "1") (pinfunction "1_1") (pintype "passive"))
      (node (ref "JP1") (pin "2") (pinfunction "2_2") (pintype "passive"))
    )
    (net (code "5") (name "ADC_TIME_SHAPE") (class "Default")
      (node (ref "IC4") (pin "3") (pinfunction "X_3") (pintype "bidirectional"))
      (node (ref "U1") (pin "9") (pinfunction "PA3_9") (pintype "bidirectional"))
    )
    (net (code "6") (name "AREF_-2.5") (class "Default")
      (node (ref "C11") (pin "1") (pinfunction "1_1") (pintype "passive"))
      (node (ref "IC3") (pin "2") (pinfunction "A_2") (pintype "passive"))
      (node (ref "R1") (pin "2") (pinfunction "2_2") (pintype "passive"))
      (node (ref "R2") (pin "2") (pinfunction "2_2") (pintype "passive"))
      (node (ref "R27") (pin "2") (pinfunction "2_2") (pintype "passive"))
      (node (ref "R3") (pin "2") (pinfunction "2_2") (pintype "passive"))
      (node (ref "R30") (pin "2") (pinfunction "2_2") (pintype "passive"))
      (node (ref "R33") (pin "2") (pinfunction "2_2") (pintype "passive"))
      (node (ref "R4") (pin "2") (pinfunction "2_2") (pintype "passive"))
      (node (ref "U$1") (pin "5") (pinfunction "P$5_5") (pintype "bidirectional"))
    )
    (net (code "7") (name "A_ADC") (class "Default")
      (node (ref "R31") (pin "2") (pinfunction "2_2") (pintype "passive"))
      (node (ref "U1") (pin "10") (pinfunction "PA4_10") (pintype "bidirectional"))
    )
    (net (code "8") (name "A_CV") (class "Default")
      (node (ref "C30") (pin "2") (pinfunction "2_2") (pintype "passive"))
      (node (ref "R14") (pin "1") (pinfunction "1_1") (pintype "passive"))
      (node (ref "U1") (pin "6") (pinfunction "PA0_6") (pintype "bidirectional"))
      (node (ref "U2") (pin "1") (pinfunction "OUT_1") (pintype "output"))
    )
    (net (code "9") (name "A_GATE") (class "Default")
      (node (ref "R13") (pin "2") (pinfunction "2_2") (pintype "passive"))
      (node (ref "U1") (pin "20") (pinfunction "PA10_20") (pintype "bidirectional"))
    )
    (net (code "10") (name "A_TRIG") (class "Default")
      (node (ref "Q4") (pin "C") (pinfunction "C_C") (pintype "passive"))
      (node (ref "U1") (pin "25") (pinfunction "PA15_25") (pintype "bidirectional"))
    )
    (net (code "11") (name "A_TRIG_IN") (class "Default")
      (node (ref "J3") (pin "P3") (pinfunction "3_P3") (pintype "passive"))
      (node (ref "R22") (pin "1") (pinfunction "1_1") (pintype "passive"))
    )
    (net (code "12") (name "B_ADC") (class "Default")
      (node (ref "R28") (pin "2") (pinfunction "2_2") (pintype "passive"))
      (node (ref "U1") (pin "11") (pinfunction "PA5_11") (pintype "bidirectional"))
    )
    (net (code "13") (name "B_CV") (class "Default")
      (node (ref "C23") (pin "2") (pinfunction "2_2") (pintype "passive"))
      (node (ref "R7") (pin "1") (pinfunction "1_1") (pintype "passive"))
      (node (ref "U1") (pin "7") (pinfunction "PA1_7") (pintype "bidirectional"))
      (node (ref "U2") (pin "8") (pinfunction "OUT_8") (pintype "output"))
    )
    (net (code "14") (name "B_CV_IN") (class "Default")
      (node (ref "J5") (pin "P3") (pinfunction "3_P3") (pintype "passive"))
      (node (ref "R25") (pin "2") (pinfunction "2_2") (pintype "passive"))
    )
    (net (code "15") (name "B_GATE") (class "Default")
      (node (ref "R12") (pin "2") (pinfunction "2_2") (pintype "passive"))
      (node (ref "U1") (pin "21") (pinfunction "PA11_21") (pintype "bidirectional"))
    )
    (net (code "16") (name "B_TRIG") (class "Default")
      (node (ref "Q3") (pin "C") (pinfunction "C_C") (pintype "passive"))
      (node (ref "U1") (pin "14") (pinfunction "PB0_14") (pintype "bidirectional"))
    )
    (net (code "17") (name "B_TRIG_IN") (class "Default")
      (node (ref "J2") (pin "P3") (pinfunction "3_P3") (pintype "passive"))
      (node (ref "R19") (pin "1") (pinfunction "1_1") (pintype "passive"))
    )
    (net (code "18") (name "C_ADC") (class "Default")
      (node (ref "R34") (pin "2") (pinfunction "2_2") (pintype "passive"))
      (node (ref "U1") (pin "12") (pinfunction "PA6_12") (pintype "bidirectional"))
    )
    (net (code "19") (name "C_CV") (class "Default")
      (node (ref "C24") (pin "2") (pinfunction "2_2") (pintype "passive"))
      (node (ref "IC4") (pin "2") (pinfunction "X6_2") (pintype "bidirectional"))
      (node (ref "JP3") (pin "4") (pinfunction "4_4") (pintype "passive"))
      (node (ref "R8") (pin "1") (pinfunction "1_1") (pintype "passive"))
      (node (ref "U2") (pin "14") (pinfunction "OUT_14") (pintype "output"))
    )
    (net (code "20") (name "C_CV_SS") (class "Default")
      (node (ref "JP3") (pin "3") (pinfunction "3_3") (pintype "passive"))
      (node (ref "U1") (pin "8") (pinfunction "PA2_8") (pintype "bidirectional"))
    )
    (net (code "21") (name "C_GATE") (class "Default")
      (node (ref "R11") (pin "2") (pinfunction "2_2") (pintype "passive"))
      (node (ref "U1") (pin "22") (pinfunction "PA12_22") (pintype "bidirectional"))
    )
    (net (code "22") (name "C_TRIG") (class "Default")
      (node (ref "Q2") (pin "C") (pinfunction "C_C") (pintype "passive"))
      (node (ref "U1") (pin "15") (pinfunction "PB1_15") (pintype "bidirectional"))
    )
    (net (code "23") (name "C_TRIG_IN") (class "Default")
      (node (ref "J1") (pin "P3") (pinfunction "3_P3") (pintype "passive"))
      (node (ref "R18") (pin "1") (pinfunction "1_1") (pintype "passive"))
    )
    (net (code "24") (name "GND") (class "Default")
      (node (ref "C1") (pin "2") (pinfunction "2_2") (pintype "passive"))
      (node (ref "C10") (pin "1") (pinfunction "1_1") (pintype "passive"))
      (node (ref "C11") (pin "2") (pinfunction "2_2") (pintype "passive"))
      (node (ref "C12") (pin "2") (pinfunction "2_2") (pintype "passive"))
      (node (ref "C13") (pin "2") (pinfunction "2_2") (pintype "passive"))
      (node (ref "C14") (pin "2") (pinfunction "2_2") (pintype "passive"))
      (node (ref "C15") (pin "2") (pinfunction "2_2") (pintype "passive"))
      (node (ref "C16") (pin "2") (pinfunction "2_2") (pintype "passive"))
      (node (ref "C17") (pin "2") (pinfunction "2_2") (pintype "passive"))
      (node (ref "C18") (pin "2") (pinfunction "2_2") (pintype "passive"))
      (node (ref "C19") (pin "2") (pinfunction "2_2") (pintype "passive"))
      (node (ref "C2") (pin "2") (pinfunction "2_2") (pintype "passive"))
      (node (ref "C20") (pin "2") (pinfunction "2_2") (pintype "passive"))
      (node (ref "C21") (pin "1") (pinfunction "1_1") (pintype "passive"))
      (node (ref "C22") (pin "1") (pinfunction "1_1") (pintype "passive"))
      (node (ref "C25") (pin "1") (pinfunction "1_1") (pintype "passive"))
      (node (ref "C26") (pin "2") (pinfunction "2_2") (pintype "passive"))
      (node (ref "C27") (pin "2") (pinfunction "2_2") (pintype "passive"))
      (node (ref "C28") (pin "2") (pinfunction "2_2") (pintype "passive"))
      (node (ref "C29") (pin "2") (pinfunction "2_2") (pintype "passive"))
      (node (ref "C3") (pin "2") (pinfunction "2_2") (pintype "passive"))
      (node (ref "C31") (pin "2") (pinfunction "2_2") (pintype "passive"))
      (node (ref "C35") (pin "2") (pinfunction "2_2") (pintype "passive"))
      (node (ref "C36") (pin "2") (pinfunction "2_2") (pintype "passive"))
      (node (ref "C37") (pin "1") (pinfunction "1_1") (pintype "passive"))
      (node (ref "C4") (pin "2") (pinfunction "2_2") (pintype "passive"))
      (node (ref "C5") (pin "2") (pinfunction "2_2") (pintype "passive"))
      (node (ref "C6") (pin "2") (pinfunction "2_2") (pintype "passive"))
      (node (ref "C7") (pin "2") (pinfunction "2_2") (pintype "passive"))
      (node (ref "C8") (pin "-") (pinfunction "-_-") (pintype "passive"))
      (node (ref "C9") (pin "1") (pinfunction "1_1") (pintype "passive"))
      (node (ref "D3") (pin "A") (pinfunction "A_A") (pintype "passive"))
      (node (ref "D4") (pin "A") (pinfunction "A_A") (pintype "passive"))
      (node (ref "D5") (pin "A") (pinfunction "A_A") (pintype "passive"))
      (node (ref "IC1") (pin "2") (pinfunction "GND_2") (pintype "passive"))
      (node (ref "IC14") (pin "13") (pinfunction "-IN_13") (pintype "input"))
      (node (ref "IC2") (pin "1") (pinfunction "GND_1") (pintype "input"))
      (node (ref "IC3") (pin "1") (pinfunction "C_1") (pintype "passive"))
      (node (ref "IC4") (pin "6") (pinfunction "INH_6") (pintype "input"))
      (node (ref "IC4") (pin "7") (pinfunction "VEE_7") (pintype "power_in"))
      (node (ref "IC4") (pin "8") (pinfunction "GND_8") (pintype "power_in"))
      (node (ref "IC5") (pin "1") (pinfunction "GND_1") (pintype "bidirectional"))
      (node (ref "IC5") (pin "21") (pinfunction "BLANK_21") (pintype "bidirectional"))
      (node (ref "IC6") (pin "11") (pinfunction "V-_11") (pintype "power_in"))
      (node (ref "IC6") (pin "12") (pinfunction "+IN_12") (pintype "input"))
      (node (ref "J1") (pin "P1") (pinfunction "1_P1") (pintype "passive"))
      (node (ref "J1") (pin "P2") (pinfunction "2_P2") (pintype "passive"))
      (node (ref "J10") (pin "P1") (pinfunction "1_P1") (pintype "passive"))
      (node (ref "J11") (pin "P1") (pinfunction "1_P1") (pintype "passive"))
      (node (ref "J12") (pin "P1") (pinfunction "1_P1") (pintype "passive"))
      (node (ref "J2") (pin "P1") (pinfunction "1_P1") (pintype "passive"))
      (node (ref "J2") (pin "P2") (pinfunction "2_P2") (pintype "passive"))
      (node (ref "J3") (pin "P1") (pinfunction "1_P1") (pintype "passive"))
      (node (ref "J3") (pin "P2") (pinfunction "2_P2") (pintype "passive"))
      (node (ref "J4") (pin "P1") (pinfunction "1_P1") (pintype "passive"))
      (node (ref "J4") (pin "P2") (pinfunction "2_P2") (pintype "passive"))
      (node (ref "J5") (pin "P1") (pinfunction "1_P1") (pintype "passive"))
      (node (ref "J5") (pin "P2") (pinfunction "2_P2") (pintype "passive"))
      (node (ref "J6") (pin "P1") (pinfunction "1_P1") (pintype "passive"))
      (node (ref "J6") (pin "P2") (pinfunction "2_P2") (pintype "passive"))
      (node (ref "J7") (pin "P1") (pinfunction "1_P1") (pintype "passive"))
      (node (ref "J8") (pin "P1") (pinfunction "1_P1") (pintype "passive"))
      (node (ref "J9") (pin "P1") (pinfunction "1_P1") (pintype "passive"))
      (node (ref "JP1") (pin "3") (pinfunction "3_3") (pintype "passive"))
      (node (ref "JP1") (pin "4") (pinfunction "4_4") (pintype "passive"))
      (node (ref "JP1") (pin "5") (pinfunction "5_5") (pintype "passive"))
      (node (ref "JP1") (pin "6") (pinfunction "6_6") (pintype "passive"))
      (node (ref "JP1") (pin "7") (pinfunction "7_7") (pintype "passive"))
      (node (ref "JP1") (pin "8") (pinfunction "8_8") (pintype "passive"))
      (node (ref "JP2") (pin "1") (pinfunction "1_1") (pintype "passive"))
      (node (ref "POT_A") (pin "P$3") (pinfunction "A_P$3") (pintype "passive"))
      (node (ref "POT_B") (pin "P$3") (pinfunction "A_P$3") (pintype "passive"))
      (node (ref "POT_C") (pin "P$3") (pinfunction "A_P$3") (pintype "passive"))
      (node (ref "Q1") (pin "2") (pinfunction "LID1_2") (pintype "power_in"))
      (node (ref "Q1") (pin "4") (pinfunction "LID2_4") (pintype "power_in"))
      (node (ref "Q2") (pin "E") (pinfunction "E_E") (pintype "passive"))
      (node (ref "Q3") (pin "E") (pinfunction "E_E") (pintype "passive"))
      (node (ref "Q4") (pin "E") (pinfunction "E_E") (pintype "passive"))
      (node (ref "R20") (pin "1") (pinfunction "1_1") (pintype "passive"))
      (node (ref "R21") (pin "1") (pinfunction "1_1") (pintype "passive"))
      (node (ref "R23") (pin "1") (pinfunction "1_1") (pintype "passive"))
      (node (ref "R45") (pin "2") (pinfunction "2_2") (pintype "passive"))
      (node (ref "R46") (pin "2") (pinfunction "2_2") (pintype "passive"))
      (node (ref "R47") (pin "2") (pinfunction "2_2") (pintype "passive"))
      (node (ref "R48") (pin "2") (pinfunction "2_2") (pintype "passive"))
      (node (ref "R49") (pin "2") (pinfunction "2_2") (pintype "passive"))
      (node (ref "R5") (pin "2") (pinfunction "2_2") (pintype "passive"))
      (node (ref "R50") (pin "2") (pinfunction "2_2") (pintype "passive"))
      (node (ref "SLD_A") (pin "1") (pinfunction "A_1") (pintype "passive"))
      (node (ref "SLD_B") (pin "1") (pinfunction "A_1") (pintype "passive"))
      (node (ref "SLD_C") (pin "1") (pinfunction "A_1") (pintype "passive"))
      (node (ref "SW_A") (pin "1") (pinfunction "1_1") (pintype "passive"))
      (node (ref "SW_A") (pin "2") (pinfunction "2_2") (pintype "passive"))
      (node (ref "SW_B") (pin "1") (pinfunction "1_1") (pintype "passive"))
      (node (ref "SW_B") (pin "2") (pinfunction "2_2") (pintype "passive"))
      (node (ref "SW_C") (pin "1") (pinfunction "1_1") (pintype "passive"))
      (node (ref "SW_C") (pin "2") (pinfunction "2_2") (pintype "passive"))
      (node (ref "U$1") (pin "6") (pinfunction "P$6_6") (pintype "bidirectional"))
      (node (ref "U1") (pin "16") (pinfunction "VSS_2_16") (pintype "power_in"))
      (node (ref "U1") (pin "31") (pinfunction "BOOT0_31") (pintype "input"))
      (node (ref "U1") (pin "32") (pinfunction "VSS_1_32") (pintype "power_in"))
      (node (ref "U2") (pin "10") (pinfunction "+IN_10") (pintype "input"))
      (node (ref "U2") (pin "11") (pinfunction "V-_11") (pintype "power_in"))
      (node (ref "U2") (pin "12") (pinfunction "+IN_12") (pintype "input"))
      (node (ref "U2") (pin "3") (pinfunction "+IN_3") (pintype "input"))
      (node (ref "U2") (pin "5") (pinfunction "+IN_5") (pintype "input"))
      (node (ref "U3") (pin "10") (pinfunction "+IN_10") (pintype "input"))
      (node (ref "U3") (pin "12") (pinfunction "+IN_12") (pintype "input"))
      (node (ref "U3") (pin "3") (pinfunction "+IN_3") (pintype "input"))
      (node (ref "U3") (pin "5") (pinfunction "+IN_5") (pintype "input"))
    )
    (net (code "25") (name "LEDS_SCK") (class "Default")
      (node (ref "IC5") (pin "3") (pinfunction "SCLK_3") (pintype "bidirectional"))
      (node (ref "U1") (pin "26") (pinfunction "PB3_26") (pintype "bidirectional"))
    )
    (net (code "26") (name "LEDS_SIN") (class "Default")
      (node (ref "IC5") (pin "2") (pinfunction "SIN_2") (pintype "bidirectional"))
      (node (ref "U1") (pin "28") (pinfunction "PB5_28") (pintype "bidirectional"))
    )
    (net (code "27") (name "LEDS_SS") (class "Default")
      (node (ref "IC5") (pin "4") (pinfunction "LAT_4") (pintype "bidirectional"))
      (node (ref "JP3") (pin "2") (pinfunction "2_2") (pintype "passive"))
    )
    (net (code "28") (name "N_U") (class "Default")
      (node (ref "U2") (pin "6") (pinfunction "-IN_6") (pintype "input"))
      (node (ref "U2") (pin "7") (pinfunction "OUT_7") (pintype "output"))
    )
    (net (code "29") (name "Net-(A-GRN)") (class "Default")
      (node (ref "A") (pin "GREEN_C") (pinfunction "GRN_GREEN_C") (pintype "bidirectional"))
      (node (ref "IC5") (pin "11") (pinfunction "OUT6_11") (pintype "bidirectional"))
    )
    (net (code "30") (name "Net-(A-RED)") (class "Default")
      (node (ref "A") (pin "RED_C") (pinfunction "RED_RED_C") (pintype "bidirectional"))
      (node (ref "IC5") (pin "10") (pinfunction "OUT5_10") (pintype "bidirectional"))
    )
    (net (code "31") (name "Net-(B-GRN)") (class "Default")
      (node (ref "B") (pin "GREEN_C") (pinfunction "GRN_GREEN_C") (pintype "bidirectional"))
      (node (ref "IC5") (pin "9") (pinfunction "OUT4_9") (pintype "bidirectional"))
    )
    (net (code "32") (name "Net-(B-RED)") (class "Default")
      (node (ref "B") (pin "RED_C") (pinfunction "RED_RED_C") (pintype "bidirectional"))
      (node (ref "IC5") (pin "8") (pinfunction "OUT3_8") (pintype "bidirectional"))
    )
    (net (code "33") (name "Net-(C-GRN)") (class "Default")
      (node (ref "C") (pin "GREEN_C") (pinfunction "GRN_GREEN_C") (pintype "bidirectional"))
      (node (ref "IC5") (pin "7") (pinfunction "OUT2_7") (pintype "bidirectional"))
    )
    (net (code "34") (name "Net-(C-RED)") (class "Default")
      (node (ref "C") (pin "RED_C") (pinfunction "RED_RED_C") (pintype "bidirectional"))
      (node (ref "IC5") (pin "6") (pinfunction "OUT1_6") (pintype "bidirectional"))
    )
    (net (code "35") (name "Net-(C1-Pad1)") (class "Default")
      (node (ref "C1") (pin "1") (pinfunction "1_1") (pintype "passive"))
      (node (ref "D1") (pin "C") (pinfunction "C_C") (pintype "passive"))
      (node (ref "L1") (pin "1") (pinfunction "1_1") (pintype "passive"))
      (node (ref "L2") (pin "2") (pinfunction "2_2") (pintype "passive"))
      (node (ref "L3") (pin "2") (pinfunction "2_2") (pintype "passive"))
    )
    (net (code "36") (name "Net-(C3-Pad1)") (class "Default")
      (node (ref "C3") (pin "1") (pinfunction "1_1") (pintype "passive"))
      (node (ref "IC2") (pin "2") (pinfunction "IN_2") (pintype "input"))
      (node (ref "IC2") (pin "4") (pinfunction "IN_4") (pintype "input"))
      (node (ref "L2") (pin "1") (pinfunction "1_1") (pintype "passive"))
    )
    (net (code "37") (name "Net-(C22-Pad2)") (class "Default")
      (node (ref "C22") (pin "2") (pinfunction "2_2") (pintype "passive"))
      (node (ref "Q1") (pin "1") (pinfunction "1_1") (pintype "passive"))
      (node (ref "R6") (pin "2") (pinfunction "2_2") (pintype "passive"))
    )
    (net (code "38") (name "Net-(D2-PadA)") (class "Default")
      (node (ref "D2") (pin "A") (pinfunction "A_A") (pintype "passive"))
      (node (ref "L4") (pin "2") (pinfunction "2_2") (pintype "passive"))
    )
    (net (code "39") (name "Net-(D3-PadC)") (class "Default")
      (node (ref "D3") (pin "C") (pinfunction "C_C") (pintype "passive"))
      (node (ref "Q2") (pin "B") (pinfunction "B_B") (pintype "passive"))
      (node (ref "R18") (pin "2") (pinfunction "2_2") (pintype "passive"))
      (node (ref "R23") (pin "2") (pinfunction "2_2") (pintype "passive"))
    )
    (net (code "40") (name "Net-(D4-PadC)") (class "Default")
      (node (ref "D4") (pin "C") (pinfunction "C_C") (pintype "passive"))
      (node (ref "Q3") (pin "B") (pinfunction "B_B") (pintype "passive"))
      (node (ref "R19") (pin "2") (pinfunction "2_2") (pintype "passive"))
      (node (ref "R20") (pin "2") (pinfunction "2_2") (pintype "passive"))
    )
    (net (code "41") (name "Net-(D5-PadC)") (class "Default")
      (node (ref "D5") (pin "C") (pinfunction "C_C") (pintype "passive"))
      (node (ref "Q4") (pin "B") (pinfunction "B_B") (pintype "passive"))
      (node (ref "R21") (pin "2") (pinfunction "2_2") (pintype "passive"))
      (node (ref "R22") (pin "2") (pinfunction "2_2") (pintype "passive"))
    )
    (net (code "42") (name "Net-(IC1-VI)") (class "Default")
      (node (ref "C5") (pin "1") (pinfunction "1_1") (pintype "passive"))
      (node (ref "IC1") (pin "1") (pinfunction "VI_1") (pintype "input"))
      (node (ref "L1") (pin "2") (pinfunction "2_2") (pintype "passive"))
    )
    (net (code "43") (name "Net-(IC4A-X0)") (class "Default")
      (node (ref "IC4") (pin "13") (pinfunction "X0_13") (pintype "bidirectional"))
      (node (ref "POT_C") (pin "P$2") (pinfunction "S_P$2") (pintype "passive"))
    )
    (net (code "44") (name "Net-(IC4A-X1)") (class "Default")
      (node (ref "IC4") (pin "14") (pinfunction "X1_14") (pintype "bidirectional"))
      (node (ref "SLD_C") (pin "2") (pinfunction "S_2") (pintype "passive"))
    )
    (net (code "45") (name "Net-(IC4A-X2)") (class "Default")
      (node (ref "IC4") (pin "15") (pinfunction "X2_15") (pintype "bidirectional"))
      (node (ref "SLD_B") (pin "2") (pinfunction "S_2") (pintype "passive"))
    )
    (net (code "46") (name "Net-(IC4A-X3)") (class "Default")
      (node (ref "IC4") (pin "12") (pinfunction "X3_12") (pintype "bidirectional"))
      (node (ref "POT_A") (pin "P$2") (pinfunction "S_P$2") (pintype "passive"))
    )
    (net (code "47") (name "Net-(IC4A-X4)") (class "Default")
      (node (ref "IC4") (pin "1") (pinfunction "X4_1") (pintype "bidirectional"))
      (node (ref "SLD_A") (pin "2") (pinfunction "S_2") (pintype "passive"))
    )
    (net (code "48") (name "Net-(IC4A-X5)") (class "Default")
      (node (ref "IC4") (pin "5") (pinfunction "X5_5") (pintype "bidirectional"))
      (node (ref "POT_B") (pin "P$2") (pinfunction "S_P$2") (pintype "passive"))
    )
    (net (code "49") (name "Net-(IC5-IREF)") (class "Default")
      (node (ref "IC5") (pin "23") (pinfunction "IREF_23") (pintype "bidirectional"))
      (node (ref "R5") (pin "1") (pinfunction "1_1") (pintype "passive"))
    )
    (net (code "50") (name "Net-(IC5-OUT7)") (class "Default")
      (node (ref "IC5") (pin "12") (pinfunction "OUT7_12") (pintype "bidirectional"))
      (node (ref "R16") (pin "2") (pinfunction "2_2") (pintype "passive"))
    )
    (net (code "51") (name "Net-(IC5-OUT8)") (class "Default")
      (node (ref "IC5") (pin "13") (pinfunction "OUT8_13") (pintype "bidirectional"))
      (node (ref "R17") (pin "2") (pinfunction "2_2") (pintype "passive"))
    )
    (net (code "52") (name "Net-(IC5-OUT9)") (class "Default")
      (node (ref "IC5") (pin "14") (pinfunction "OUT9_14") (pintype "bidirectional"))
      (node (ref "R15") (pin "2") (pinfunction "2_2") (pintype "passive"))
    )
    (net (code "53") (name "Net-(IC5-VCC)") (class "Default")
      (node (ref "C14") (pin "1") (pinfunction "1_1") (pintype "passive"))
      (node (ref "C15") (pin "1") (pinfunction "1_1") (pintype "passive"))
      (node (ref "IC5") (pin "24") (pinfunction "VCC_24") (pintype "bidirectional"))
      (node (ref "L5") (pin "1") (pinfunction "1_1") (pintype "passive"))
    )
    (net (code "54") (name "Net-(IC6A-+IN)") (class "Default")
      (node (ref "IC6") (pin "3") (pinfunction "+IN_3") (pintype "input"))
      (node (ref "R44") (pin "2") (pinfunction "2_2") (pintype "passive"))
      (node (ref "R47") (pin "1") (pinfunction "1_1") (pintype "passive"))
    )
    (net (code "55") (name "Net-(IC6A--IN)") (class "Default")
      (node (ref "IC6") (pin "2") (pinfunction "-IN_2") (pintype "input"))
      (node (ref "R13") (pin "1") (pinfunction "1_1") (pintype "passive"))
    )
    (net (code "56") (name "Net-(IC6A-OUT)") (class "Default")
      (node (ref "IC6") (pin "1") (pinfunction "OUT_1") (pintype "output"))
      (node (ref "R39") (pin "2") (pinfunction "2_2") (pintype "passive"))
      (node (ref "R44") (pin "1") (pinfunction "1_1") (pintype "passive"))
    )
    (net (code "57") (name "Net-(IC6B-+IN)") (class "Default")
      (node (ref "IC6") (pin "5") (pinfunction "+IN_5") (pintype "input"))
      (node (ref "R41") (pin "2") (pinfunction "2_2") (pintype "passive"))
      (node (ref "R46") (pin "1") (pinfunction "1_1") (pintype "passive"))
    )
    (net (code "58") (name "Net-(IC6B--IN)") (class "Default")
      (node (ref "IC6") (pin "6") (pinfunction "-IN_6") (pintype "input"))
      (node (ref "R12") (pin "1") (pinfunction "1_1") (pintype "passive"))
    )
    (net (code "59") (name "Net-(IC6B-OUT)") (class "Default")
      (node (ref "IC6") (pin "7") (pinfunction "OUT_7") (pintype "output"))
      (node (ref "R38") (pin "2") (pinfunction "2_2") (pintype "passive"))
      (node (ref "R41") (pin "1") (pinfunction "1_1") (pintype "passive"))
    )
    (net (code "60") (name "Net-(IC6C-+IN)") (class "Default")
      (node (ref "IC6") (pin "10") (pinfunction "+IN_10") (pintype "input"))
      (node (ref "R36") (pin "2") (pinfunction "2_2") (pintype "passive"))
      (node (ref "R45") (pin "1") (pinfunction "1_1") (pintype "passive"))
    )
    (net (code "61") (name "Net-(IC6C--IN)") (class "Default")
      (node (ref "IC6") (pin "9") (pinfunction "-IN_9") (pintype "input"))
      (node (ref "R11") (pin "1") (pinfunction "1_1") (pintype "passive"))
    )
    (net (code "62") (name "Net-(IC6C-OUT)") (class "Default")
      (node (ref "IC6") (pin "8") (pinfunction "OUT_8") (pintype "output"))
      (node (ref "R36") (pin "1") (pinfunction "1_1") (pintype "passive"))
      (node (ref "R37") (pin "2") (pinfunction "2_2") (pintype "passive"))
    )
    (net (code "63") (name "Net-(IC6D--IN)") (class "Default")
      (node (ref "IC6") (pin "13") (pinfunction "-IN_13") (pintype "input"))
      (node (ref "IC6") (pin "14") (pinfunction "OUT_14") (pintype "output"))
    )
    (net (code "64") (name "Net-(IC14B-+IN)") (class "Default")
      (node (ref "C32") (pin "2") (pinfunction "2_2") (pintype "passive"))
      (node (ref "IC14") (pin "5") (pinfunction "+IN_5") (pintype "input"))
      (node (ref "R42") (pin "2") (pinfunction "2_2") (pintype "passive"))
      (node (ref "U3") (pin "7") (pinfunction "OUT_7") (pintype "output"))
    )
    (net (code "65") (name "Net-(IC14B--IN)") (class "Default")
      (node (ref "IC14") (pin "6") (pinfunction "-IN_6") (pintype "input"))
      (node (ref "LED_OUT_2") (pin "2") (pinfunction "2_2") (pintype "bidirectional"))
      (node (ref "R49") (pin "1") (pinfunction "1_1") (pintype "passive"))
    )
    (net (code "66") (name "Net-(IC14B-OUT)") (class "Default")
      (node (ref "IC14") (pin "7") (pinfunction "OUT_7") (pintype "output"))
      (node (ref "LED_OUT_2") (pin "1") (pinfunction "1_1") (pintype "bidirectional"))
    )
    (net (code "67") (name "Net-(IC14D-+IN)") (class "Default")
      (node (ref "IC14") (pin "12") (pinfunction "+IN_12") (pintype "input"))
      (node (ref "IC14") (pin "14") (pinfunction "OUT_14") (pintype "output"))
    )
    (net (code "68") (name "Net-(J4-3)") (class "Default")
      (node (ref "J4") (pin "P3") (pinfunction "3_P3") (pintype "passive"))
      (node (ref "R24") (pin "2") (pinfunction "2_2") (pintype "passive"))
    )
    (net (code "69") (name "Net-(J6-3)") (class "Default")
      (node (ref "J6") (pin "P3") (pinfunction "3_P3") (pintype "passive"))
      (node (ref "R26") (pin "2") (pinfunction "2_2") (pintype "passive"))
    )
    (net (code "70") (name "Net-(J7-3)") (class "Default")
      (node (ref "J7") (pin "P3") (pinfunction "3_P3") (pintype "passive"))
      (node (ref "R37") (pin "1") (pinfunction "1_1") (pintype "passive"))
    )
    (net (code "71") (name "Net-(J8-3)") (class "Default")
      (node (ref "J8") (pin "P3") (pinfunction "3_P3") (pintype "passive"))
      (node (ref "R38") (pin "1") (pinfunction "1_1") (pintype "passive"))
    )
    (net (code "72") (name "Net-(J9-3)") (class "Default")
      (node (ref "J9") (pin "P3") (pinfunction "3_P3") (pintype "passive"))
      (node (ref "R39") (pin "1") (pinfunction "1_1") (pintype "passive"))
    )
    (net (code "73") (name "Net-(J10-3)") (class "Default")
      (node (ref "J10") (pin "P3") (pinfunction "3_P3") (pintype "passive"))
      (node (ref "R35") (pin "1") (pinfunction "1_1") (pintype "passive"))
      (node (ref "R40") (pin "1") (pinfunction "1_1") (pintype "passive"))
    )
    (net (code "74") (name "Net-(J11-3)") (class "Default")
      (node (ref "J11") (pin "P3") (pinfunction "3_P3") (pintype "passive"))
      (node (ref "R29") (pin "1") (pinfunction "1_1") (pintype "passive"))
      (node (ref "R42") (pin "1") (pinfunction "1_1") (pintype "passive"))
    )
    (net (code "75") (name "Net-(J12-3)") (class "Default")
      (node (ref "J12") (pin "P3") (pinfunction "3_P3") (pintype "passive"))
      (node (ref "R32") (pin "1") (pinfunction "1_1") (pintype "passive"))
      (node (ref "R43") (pin "1") (pinfunction "1_1") (pintype "passive"))
    )
    (net (code "76") (name "Net-(LED_OUT_1-Pad2)") (class "Default")
      (node (ref "LED_OUT_1") (pin "2") (pinfunction "2_2") (pintype "bidirectional"))
      (node (ref "R48") (pin "1") (pinfunction "1_1") (pintype "passive"))
    )
    (net (code "77") (name "Net-(LED_OUT_3-Pad2)") (class "Default")
      (node (ref "LED_OUT_3") (pin "2") (pinfunction "2_2") (pintype "bidirectional"))
      (node (ref "R50") (pin "1") (pinfunction "1_1") (pintype "passive"))
    )
    (net (code "78") (name "Net-(Q1B-2)") (class "Default")
      (node (ref "C21") (pin "2") (pinfunction "2_2") (pintype "passive"))
      (node (ref "Q1") (pin "3") (pinfunction "2_3") (pintype "passive"))
      (node (ref "R9") (pin "2") (pinfunction "2_2") (pintype "passive"))
    )
    (net (code "79") (name "Net-(SLD_AA-A)") (class "Default")
      (node (ref "SLD_A") (pin "B") (pinfunction "A_B") (pintype "passive"))
      (node (ref "SLD_B") (pin "B") (pinfunction "A_B") (pintype "passive"))
      (node (ref "SLD_C") (pin "B") (pinfunction "A_B") (pintype "passive"))
    )
    (net (code "80") (name "Net-(SLD_AA-C)") (class "Default")
      (node (ref "R16") (pin "1") (pinfunction "1_1") (pintype "passive"))
      (node (ref "SLD_A") (pin "E") (pinfunction "C_E") (pintype "passive"))
    )
    (net (code "81") (name "Net-(SLD_BA-C)") (class "Default")
      (node (ref "R17") (pin "1") (pinfunction "1_1") (pintype "passive"))
      (node (ref "SLD_B") (pin "E") (pinfunction "C_E") (pintype "passive"))
    )
    (net (code "82") (name "Net-(SLD_CA-C)") (class "Default")
      (node (ref "R15") (pin "1") (pinfunction "1_1") (pintype "passive"))
      (node (ref "SLD_C") (pin "E") (pinfunction "C_E") (pintype "passive"))
    )
    (net (code "83") (name "Net-(U1-PF0{slash}OSC_IN)") (class "Default")
      (node (ref "R9") (pin "1") (pinfunction "1_1") (pintype "passive"))
      (node (ref "U1") (pin "2") (pinfunction "PF0/OSC_IN_2") (pintype "bidirectional"))
    )
    (net (code "84") (name "Net-(U1-PF1{slash}OSC_OUT)") (class "Default")
      (node (ref "R6") (pin "1") (pinfunction "1_1") (pintype "passive"))
      (node (ref "U1") (pin "3") (pinfunction "PF1/OSC_OUT_3") (pintype "bidirectional"))
    )
    (net (code "85") (name "Net-(U2A--IN)") (class "Default")
      (node (ref "C30") (pin "1") (pinfunction "1_1") (pintype "passive"))
      (node (ref "R14") (pin "2") (pinfunction "2_2") (pintype "passive"))
      (node (ref "R2") (pin "1") (pinfunction "1_1") (pintype "passive"))
      (node (ref "R26") (pin "1") (pinfunction "1_1") (pintype "passive"))
      (node (ref "U2") (pin "2") (pinfunction "-IN_2") (pintype "input"))
    )
    (net (code "86") (name "Net-(U2C--IN)") (class "Default")
      (node (ref "C23") (pin "1") (pinfunction "1_1") (pintype "passive"))
      (node (ref "R25") (pin "1") (pinfunction "1_1") (pintype "passive"))
      (node (ref "R3") (pin "1") (pinfunction "1_1") (pintype "passive"))
      (node (ref "R7") (pin "2") (pinfunction "2_2") (pintype "passive"))
      (node (ref "U2") (pin "9") (pinfunction "-IN_9") (pintype "input"))
    )
    (net (code "87") (name "Net-(U2D--IN)") (class "Default")
      (node (ref "C24") (pin "1") (pinfunction "1_1") (pintype "passive"))
      (node (ref "R24") (pin "1") (pinfunction "1_1") (pintype "passive"))
      (node (ref "R4") (pin "1") (pinfunction "1_1") (pintype "passive"))
      (node (ref "R8") (pin "2") (pinfunction "2_2") (pintype "passive"))
      (node (ref "U2") (pin "13") (pinfunction "-IN_13") (pintype "input"))
    )
    (net (code "88") (name "Net-(U3A--IN)") (class "Default")
      (node (ref "C33") (pin "1") (pinfunction "1_1") (pintype "passive"))
      (node (ref "R30") (pin "1") (pinfunction "1_1") (pintype "passive"))
      (node (ref "R31") (pin "1") (pinfunction "1_1") (pintype "passive"))
      (node (ref "R32") (pin "2") (pinfunction "2_2") (pintype "passive"))
      (node (ref "U3") (pin "2") (pinfunction "-IN_2") (pintype "input"))
    )
    (net (code "89") (name "Net-(U3A-OUT)") (class "Default")
      (node (ref "C33") (pin "2") (pinfunction "2_2") (pintype "passive"))
      (node (ref "R43") (pin "2") (pinfunction "2_2") (pintype "passive"))
      (node (ref "U3") (pin "1") (pinfunction "OUT_1") (pintype "output"))
    )
    (net (code "90") (name "Net-(U3B--IN)") (class "Default")
      (node (ref "C32") (pin "1") (pinfunction "1_1") (pintype "passive"))
      (node (ref "R27") (pin "1") (pinfunction "1_1") (pintype "passive"))
      (node (ref "R28") (pin "1") (pinfunction "1_1") (pintype "passive"))
      (node (ref "R29") (pin "2") (pinfunction "2_2") (pintype "passive"))
      (node (ref "U3") (pin "6") (pinfunction "-IN_6") (pintype "input"))
    )
    (net (code "91") (name "Net-(U3C--IN)") (class "Default")
      (node (ref "C34") (pin "1") (pinfunction "1_1") (pintype "passive"))
      (node (ref "R33") (pin "1") (pinfunction "1_1") (pintype "passive"))
      (node (ref "R34") (pin "1") (pinfunction "1_1") (pintype "passive"))
      (node (ref "R35") (pin "2") (pinfunction "2_2") (pintype "passive"))
      (node (ref "U3") (pin "9") (pinfunction "-IN_9") (pintype "input"))
    )
    (net (code "92") (name "Net-(U3C-OUT)") (class "Default")
      (node (ref "C34") (pin "2") (pinfunction "2_2") (pintype "passive"))
      (node (ref "R40") (pin "2") (pinfunction "2_2") (pintype "passive"))
      (node (ref "U3") (pin "8") (pinfunction "OUT_8") (pintype "output"))
    )
    (net (code "93") (name "Net-(U3D--IN)") (class "Default")
      (node (ref "U3") (pin "13") (pinfunction "-IN_13") (pintype "input"))
      (node (ref "U3") (pin "14") (pinfunction "OUT_14") (pintype "output"))
    )
    (net (code "94") (name "POTS_ADDR_A") (class "Default")
      (node (ref "IC4") (pin "11") (pinfunction "A_11") (pintype "input"))
      (node (ref "U1") (pin "13") (pinfunction "PA7_13") (pintype "bidirectional"))
    )
    (net (code "95") (name "POTS_ADDR_B") (class "Default")
      (node (ref "IC4") (pin "10") (pinfunction "B_10") (pintype "input"))
      (node (ref "U1") (pin "18") (pinfunction "PA8_18") (pintype "bidirectional"))
    )
    (net (code "96") (name "POTS_ADDR_C") (class "Default")
      (node (ref "IC4") (pin "9") (pinfunction "C_9") (pintype "input"))
      (node (ref "U1") (pin "19") (pinfunction "PA9_19") (pintype "bidirectional"))
    )
    (net (code "97") (name "RESET") (class "Default")
      (node (ref "C28") (pin "1") (pinfunction "1_1") (pintype "passive"))
      (node (ref "JP2") (pin "4") (pinfunction "4_4") (pintype "passive"))
      (node (ref "R10") (pin "2") (pinfunction "2_2") (pintype "passive"))
      (node (ref "U1") (pin "4") (pinfunction "NRST_4") (pintype "bidirectional"))
    )
    (net (code "98") (name "SWCLK") (class "Default")
      (node (ref "JP2") (pin "3") (pinfunction "3_3") (pintype "passive"))
      (node (ref "U1") (pin "24") (pinfunction "PA14_24") (pintype "bidirectional"))
    )
    (net (code "99") (name "SWDIO_SS") (class "Default")
      (node (ref "JP2") (pin "2") (pinfunction "2_2") (pintype "passive"))
      (node (ref "JP3") (pin "1") (pinfunction "1_1") (pintype "passive"))
      (node (ref "U1") (pin "23") (pinfunction "PA13_23") (pintype "bidirectional"))
    )
    (net (code "100") (name "SW_MODE_A") (class "Default")
      (node (ref "SW_A") (pin "3") (pinfunction "3_3") (pintype "passive"))
      (node (ref "SW_A") (pin "4") (pinfunction "4_4") (pintype "passive"))
      (node (ref "U1") (pin "27") (pinfunction "PB4_27") (pintype "bidirectional"))
    )
    (net (code "101") (name "SW_MODE_B") (class "Default")
      (node (ref "SW_B") (pin "3") (pinfunction "3_3") (pintype "passive"))
      (node (ref "SW_B") (pin "4") (pinfunction "4_4") (pintype "passive"))
      (node (ref "U1") (pin "29") (pinfunction "PB6_29") (pintype "bidirectional"))
    )
    (net (code "102") (name "SW_MODE_C") (class "Default")
      (node (ref "SW_C") (pin "3") (pinfunction "3_3") (pintype "passive"))
      (node (ref "SW_C") (pin "4") (pinfunction "4_4") (pintype "passive"))
      (node (ref "U1") (pin "30") (pinfunction "PB7_30") (pintype "bidirectional"))
    )
    (net (code "103") (name "VCC") (class "Default")
      (node (ref "C2") (pin "1") (pinfunction "1_1") (pintype "passive"))
      (node (ref "C31") (pin "1") (pinfunction "1_1") (pintype "passive"))
      (node (ref "C35") (pin "1") (pinfunction "1_1") (pintype "passive"))
      (node (ref "C36") (pin "1") (pinfunction "1_1") (pintype "passive"))
      (node (ref "C4") (pin "1") (pinfunction "1_1") (pintype "passive"))
      (node (ref "IC14") (pin "4") (pinfunction "V+_4") (pintype "power_in"))
      (node (ref "IC6") (pin "4") (pinfunction "V+_4") (pintype "power_in"))
      (node (ref "L3") (pin "1") (pinfunction "1_1") (pintype "passive"))
      (node (ref "U$1") (pin "1") (pinfunction "P$1_1") (pintype "bidirectional"))
      (node (ref "U3") (pin "4") (pinfunction "V+_4") (pintype "power_in"))
    )
    (net (code "104") (name "VEE") (class "Default")
      (node (ref "C10") (pin "2") (pinfunction "2_2") (pintype "passive"))
      (node (ref "C25") (pin "2") (pinfunction "2_2") (pintype "passive"))
      (node (ref "C37") (pin "2") (pinfunction "2_2") (pintype "passive"))
      (node (ref "C9") (pin "2") (pinfunction "2_2") (pintype "passive"))
      (node (ref "IC14") (pin "11") (pinfunction "V-_11") (pintype "power_in"))
      (node (ref "L4") (pin "1") (pinfunction "1_1") (pintype "passive"))
      (node (ref "R1") (pin "1") (pinfunction "1_1") (pintype "passive"))
      (node (ref "U$1") (pin "2") (pinfunction "P$2_2") (pintype "bidirectional"))
      (node (ref "U3") (pin "11") (pinfunction "V-_11") (pintype "power_in"))
    )
    (net (code "105") (name "unconnected-(IC4A-X7-Pad4)") (class "Default")
      (node (ref "IC4") (pin "4") (pinfunction "X7_4") (pintype "bidirectional"))
    )
    (net (code "106") (name "unconnected-(IC5-OUT0-Pad5)") (class "Default")
      (node (ref "IC5") (pin "5") (pinfunction "OUT0_5") (pintype "bidirectional"))
    )
    (net (code "107") (name "unconnected-(IC5-OUT10-Pad15)") (class "Default")
      (node (ref "IC5") (pin "15") (pinfunction "OUT10_15") (pintype "bidirectional"))
    )
    (net (code "108") (name "unconnected-(IC5-OUT11-Pad16)") (class "Default")
      (node (ref "IC5") (pin "16") (pinfunction "OUT11_16") (pintype "bidirectional"))
    )
    (net (code "109") (name "unconnected-(IC5-OUT12-Pad17)") (class "Default")
      (node (ref "IC5") (pin "17") (pinfunction "OUT12_17") (pintype "bidirectional"))
    )
    (net (code "110") (name "unconnected-(IC5-OUT13-Pad18)") (class "Default")
      (node (ref "IC5") (pin "18") (pinfunction "OUT13_18") (pintype "bidirectional"))
    )
    (net (code "111") (name "unconnected-(IC5-OUT14-Pad19)") (class "Default")
      (node (ref "IC5") (pin "19") (pinfunction "OUT14_19") (pintype "bidirectional"))
    )
    (net (code "112") (name "unconnected-(IC5-OUT15-Pad20)") (class "Default")
      (node (ref "IC5") (pin "20") (pinfunction "OUT15_20") (pintype "bidirectional"))
    )
    (net (code "113") (name "unconnected-(IC5-SOUT-Pad22)") (class "Default")
      (node (ref "IC5") (pin "22") (pinfunction "SOUT_22") (pintype "bidirectional"))
    )
    (net (code "114") (name "unconnected-(IC14A-+IN-Pad3)") (class "Default")
      (node (ref "IC14") (pin "3") (pinfunction "+IN_3") (pintype "input"))
    )
    (net (code "115") (name "unconnected-(IC14A--IN-Pad2)") (class "Default")
      (node (ref "IC14") (pin "2") (pinfunction "-IN_2") (pintype "input"))
    )
    (net (code "116") (name "unconnected-(IC14A-OUT-Pad1)") (class "Default")
      (node (ref "IC14") (pin "1") (pinfunction "OUT_1") (pintype "output"))
    )
    (net (code "117") (name "unconnected-(IC14C-+IN-Pad10)") (class "Default")
      (node (ref "IC14") (pin "10") (pinfunction "+IN_10") (pintype "input"))
    )
    (net (code "118") (name "unconnected-(IC14C--IN-Pad9)") (class "Default")
      (node (ref "IC14") (pin "9") (pinfunction "-IN_9") (pintype "input"))
    )
    (net (code "119") (name "unconnected-(IC14C-OUT-Pad8)") (class "Default")
      (node (ref "IC14") (pin "8") (pinfunction "OUT_8") (pintype "output"))
    )
    (net (code "120") (name "unconnected-(J7-2-PadP2)") (class "Default")
      (node (ref "J7") (pin "P2") (pinfunction "2_P2") (pintype "passive"))
    )
    (net (code "121") (name "unconnected-(J8-2-PadP2)") (class "Default")
      (node (ref "J8") (pin "P2") (pinfunction "2_P2") (pintype "passive"))
    )
    (net (code "122") (name "unconnected-(J9-2-PadP2)") (class "Default")
      (node (ref "J9") (pin "P2") (pinfunction "2_P2") (pintype "passive"))
    )
    (net (code "123") (name "unconnected-(J10-2-PadP2)") (class "Default")
      (node (ref "J10") (pin "P2") (pinfunction "2_P2") (pintype "passive"))
    )
    (net (code "124") (name "unconnected-(J11-2-PadP2)") (class "Default")
      (node (ref "J11") (pin "P2") (pinfunction "2_P2") (pintype "passive"))
    )
    (net (code "125") (name "unconnected-(J12-2-PadP2)") (class "Default")
      (node (ref "J12") (pin "P2") (pinfunction "2_P2") (pintype "passive"))
    )
    (net (code "126") (name "unconnected-(LED_OUT_1-Pad1)") (class "Default")
      (node (ref "LED_OUT_1") (pin "1") (pinfunction "1_1") (pintype "bidirectional"))
    )
    (net (code "127") (name "unconnected-(LED_OUT_3-Pad1)") (class "Default")
      (node (ref "LED_OUT_3") (pin "1") (pinfunction "1_1") (pintype "bidirectional"))
    )
  )
)
